# HABEXpico8.net
KiCad netlist of a schematic drawn in EAGLE
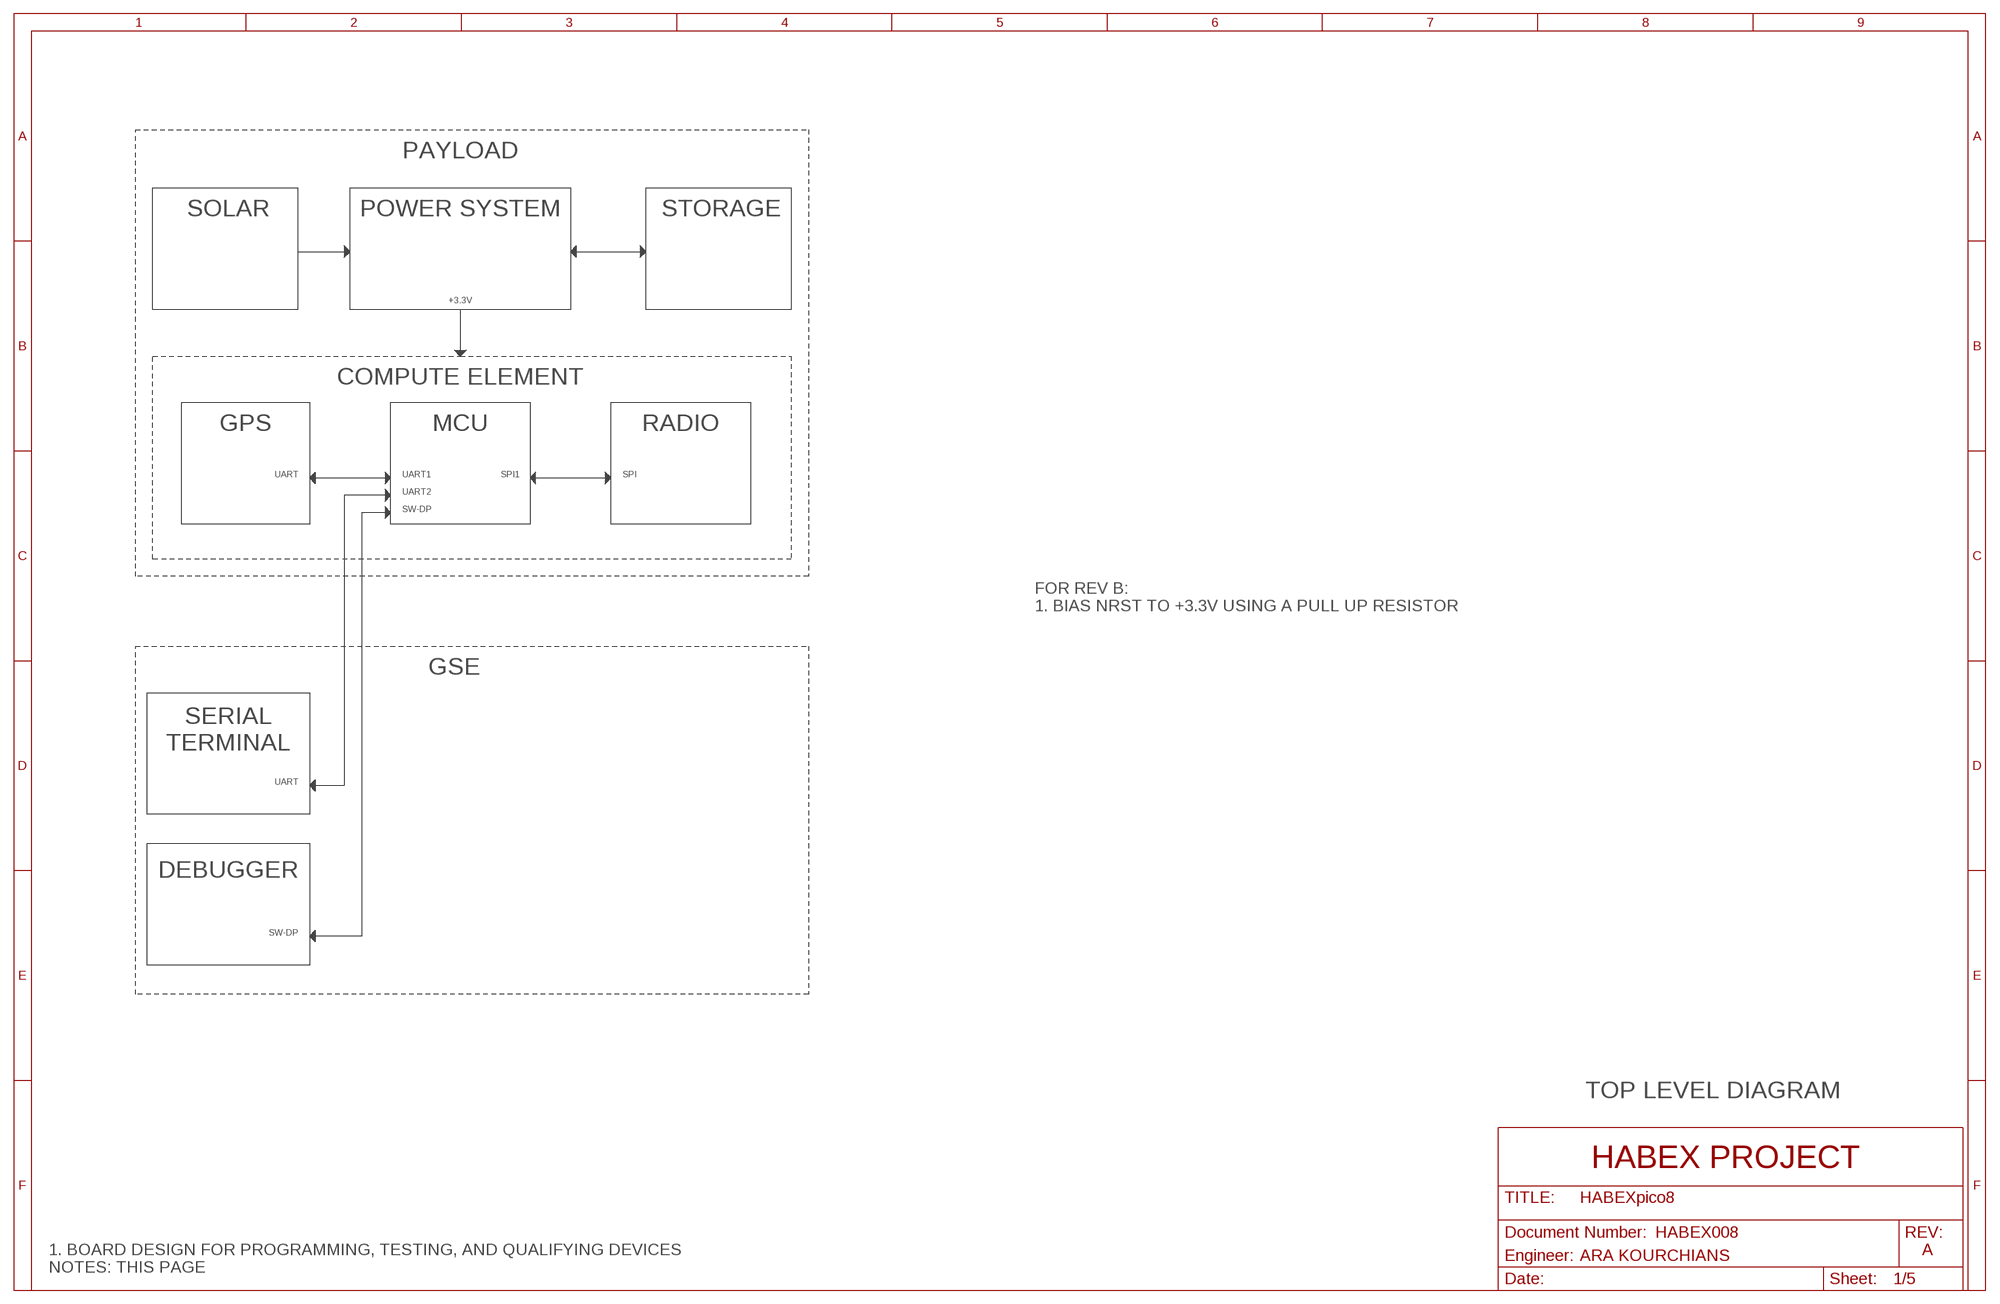
[diagram p0: schematic, sheet 1]
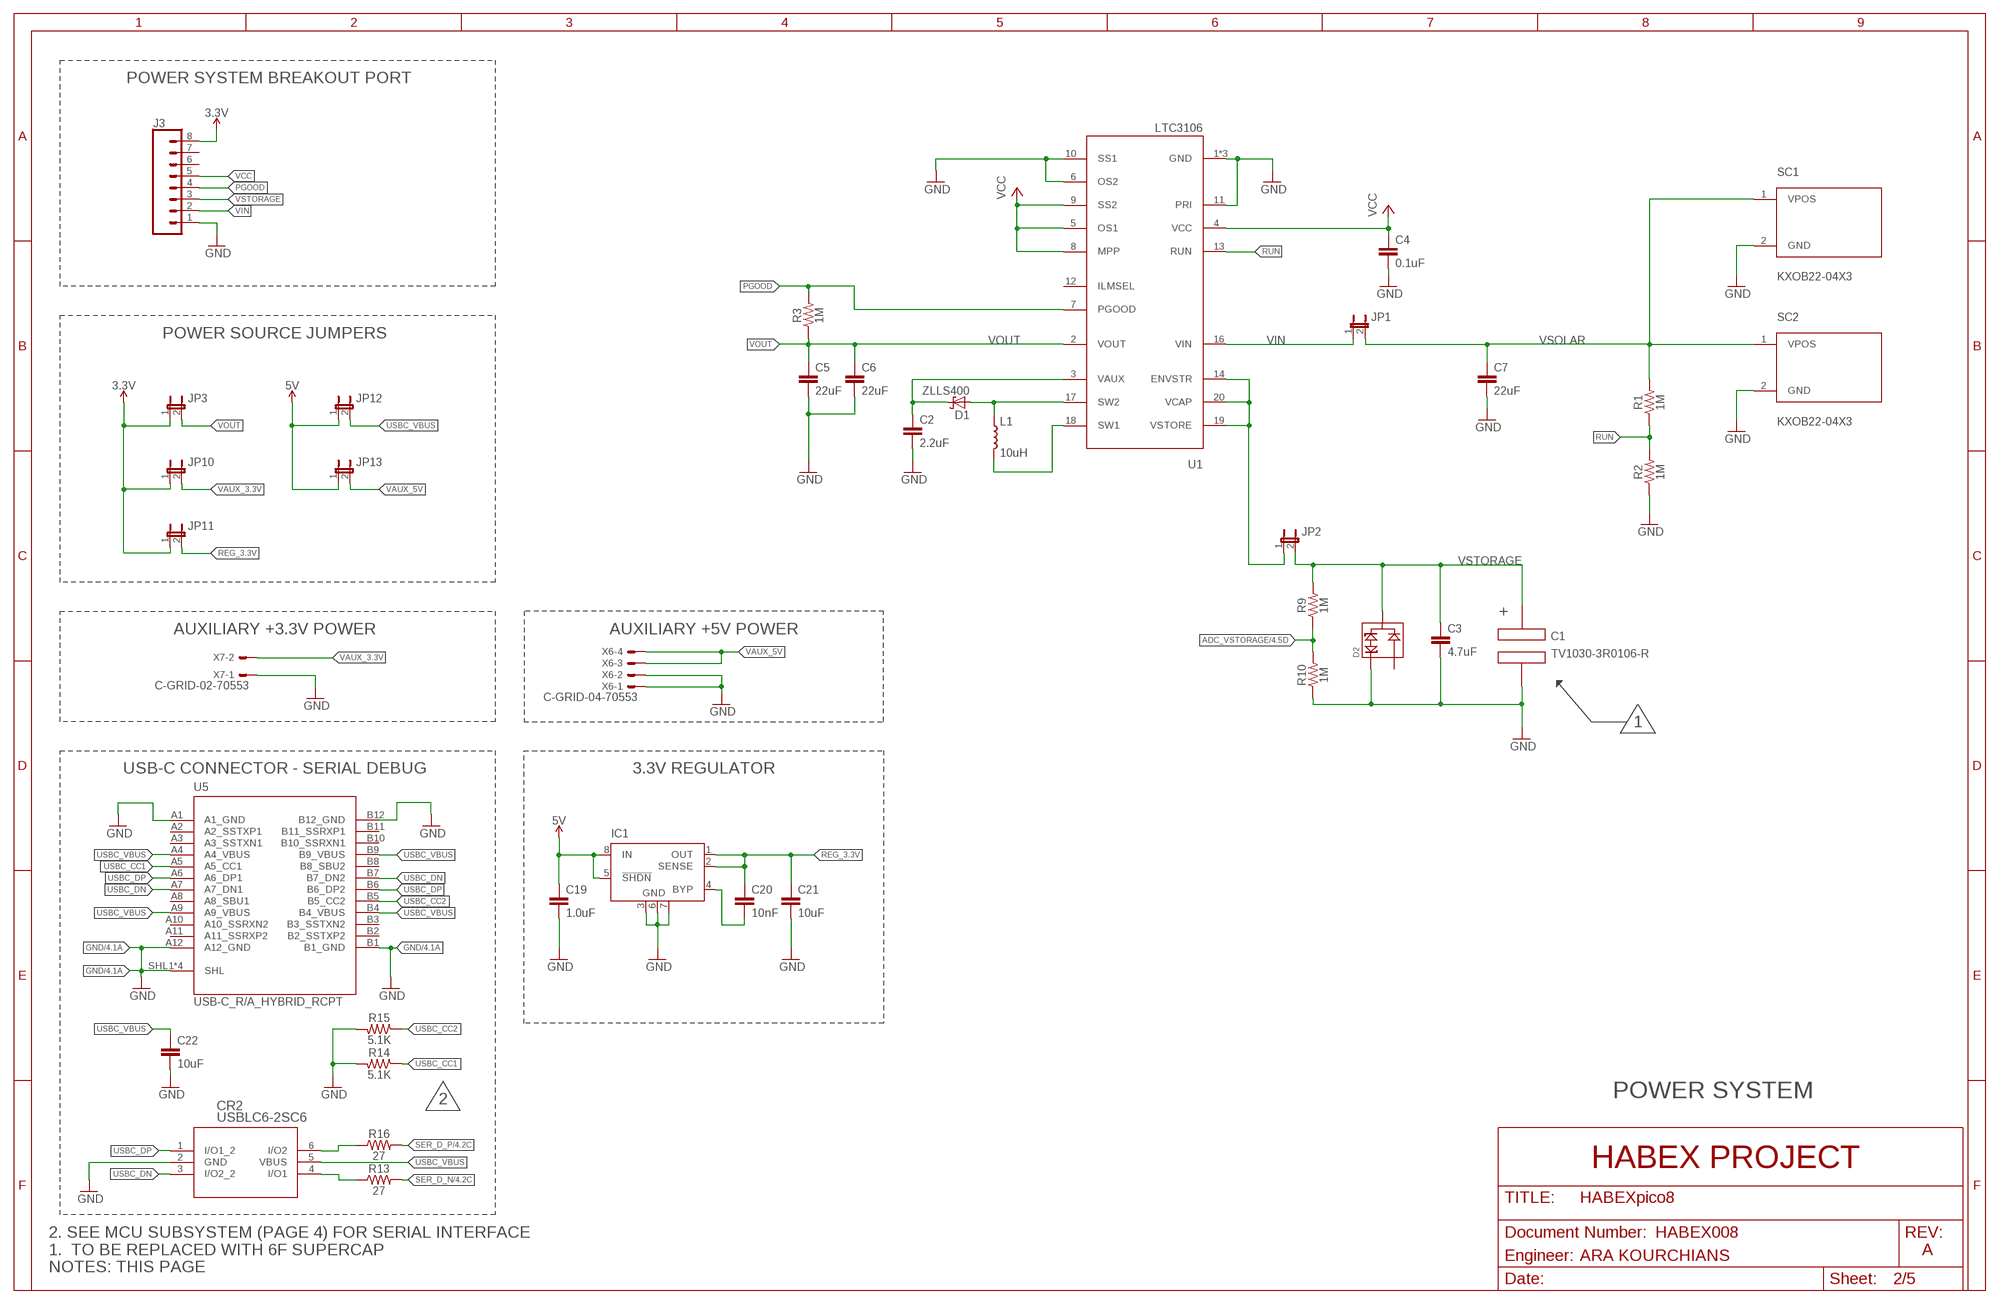
[diagram p1: schematic, sheet 2]
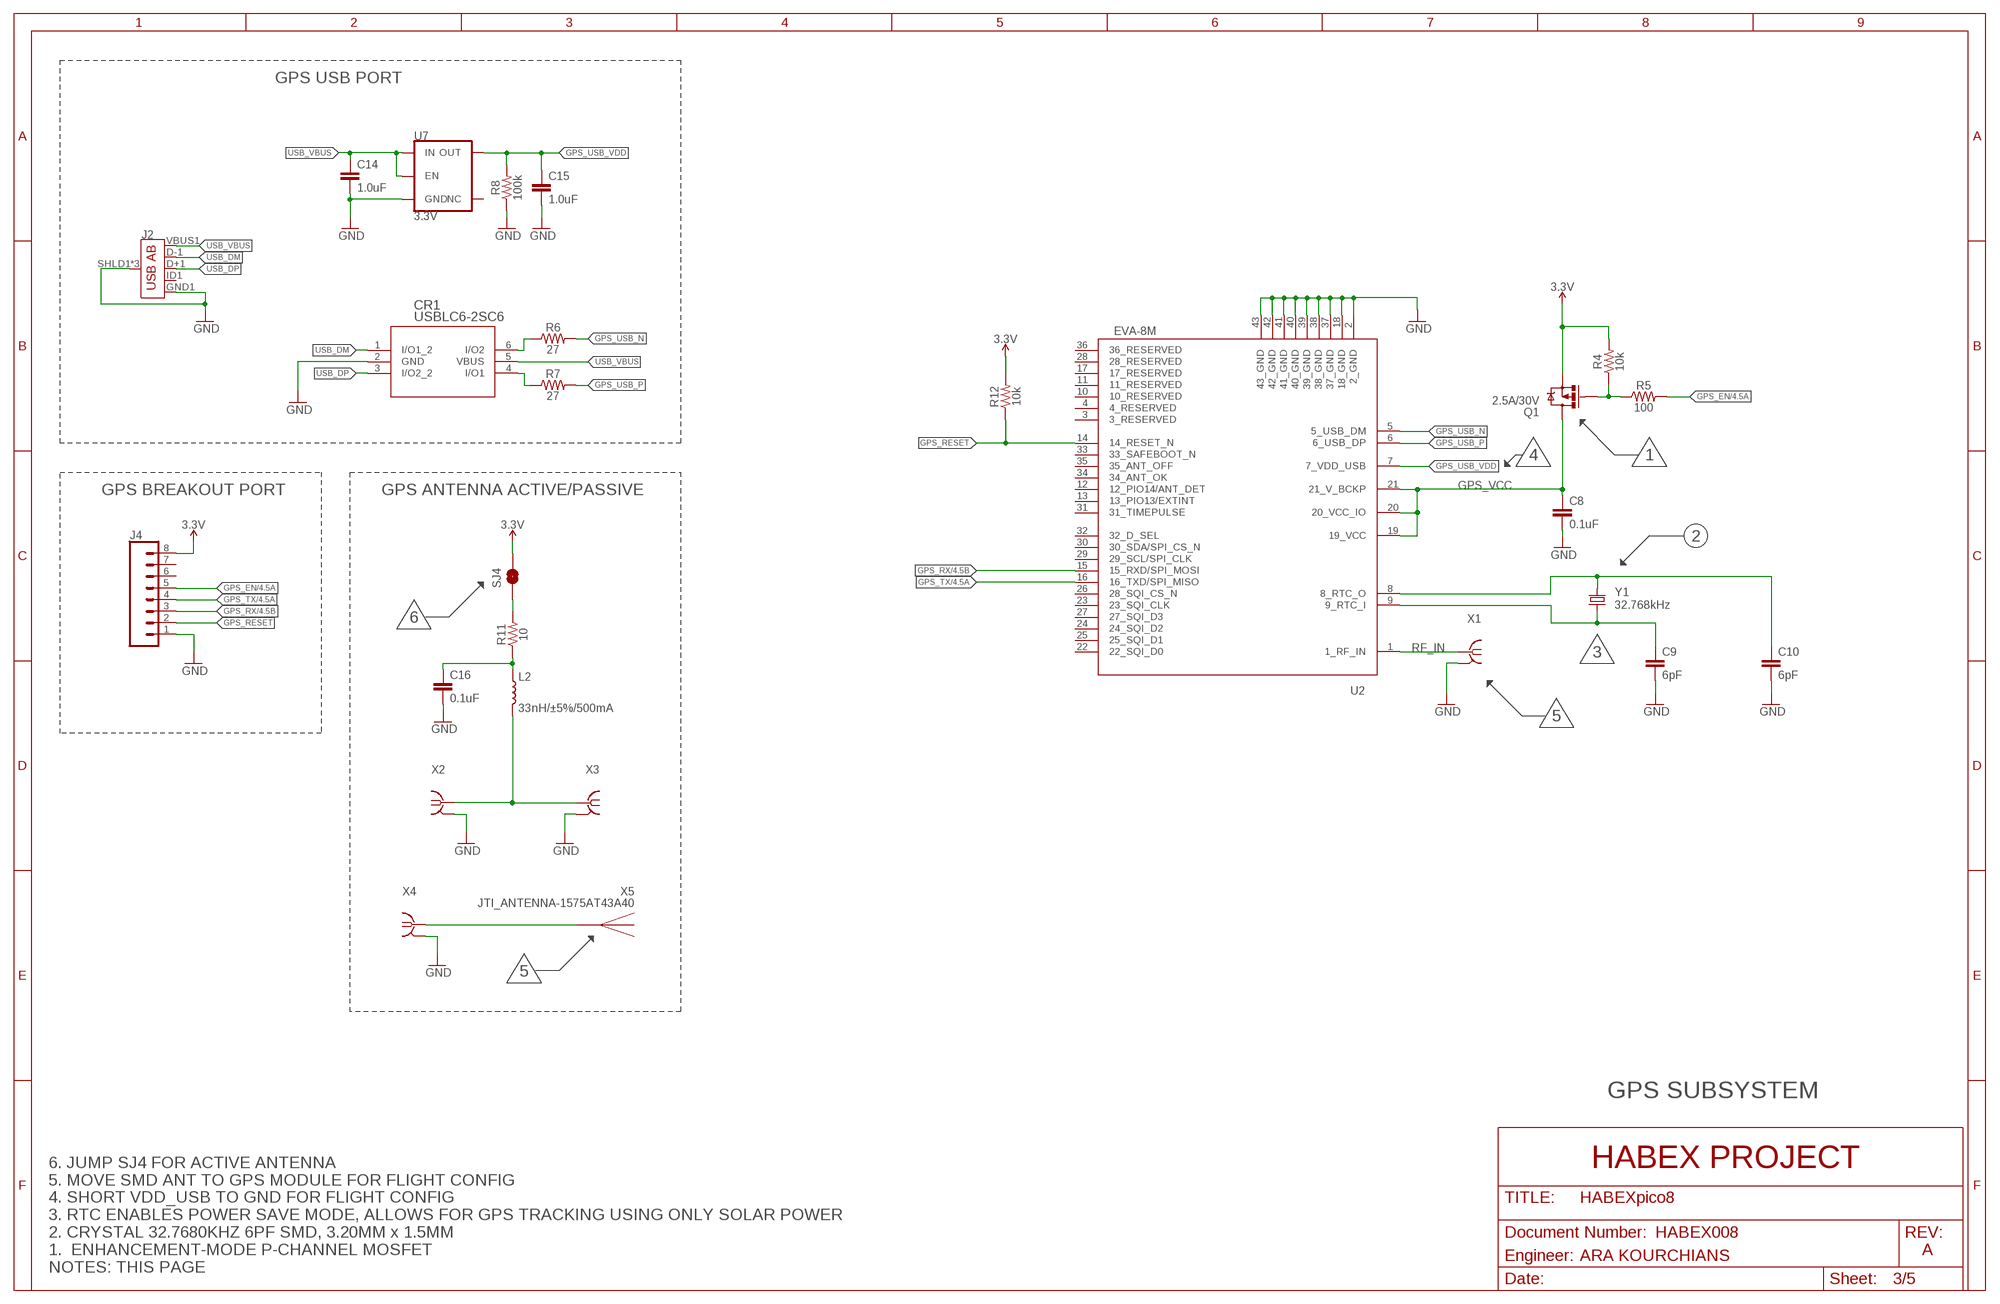
[diagram p2: schematic, sheet 3]
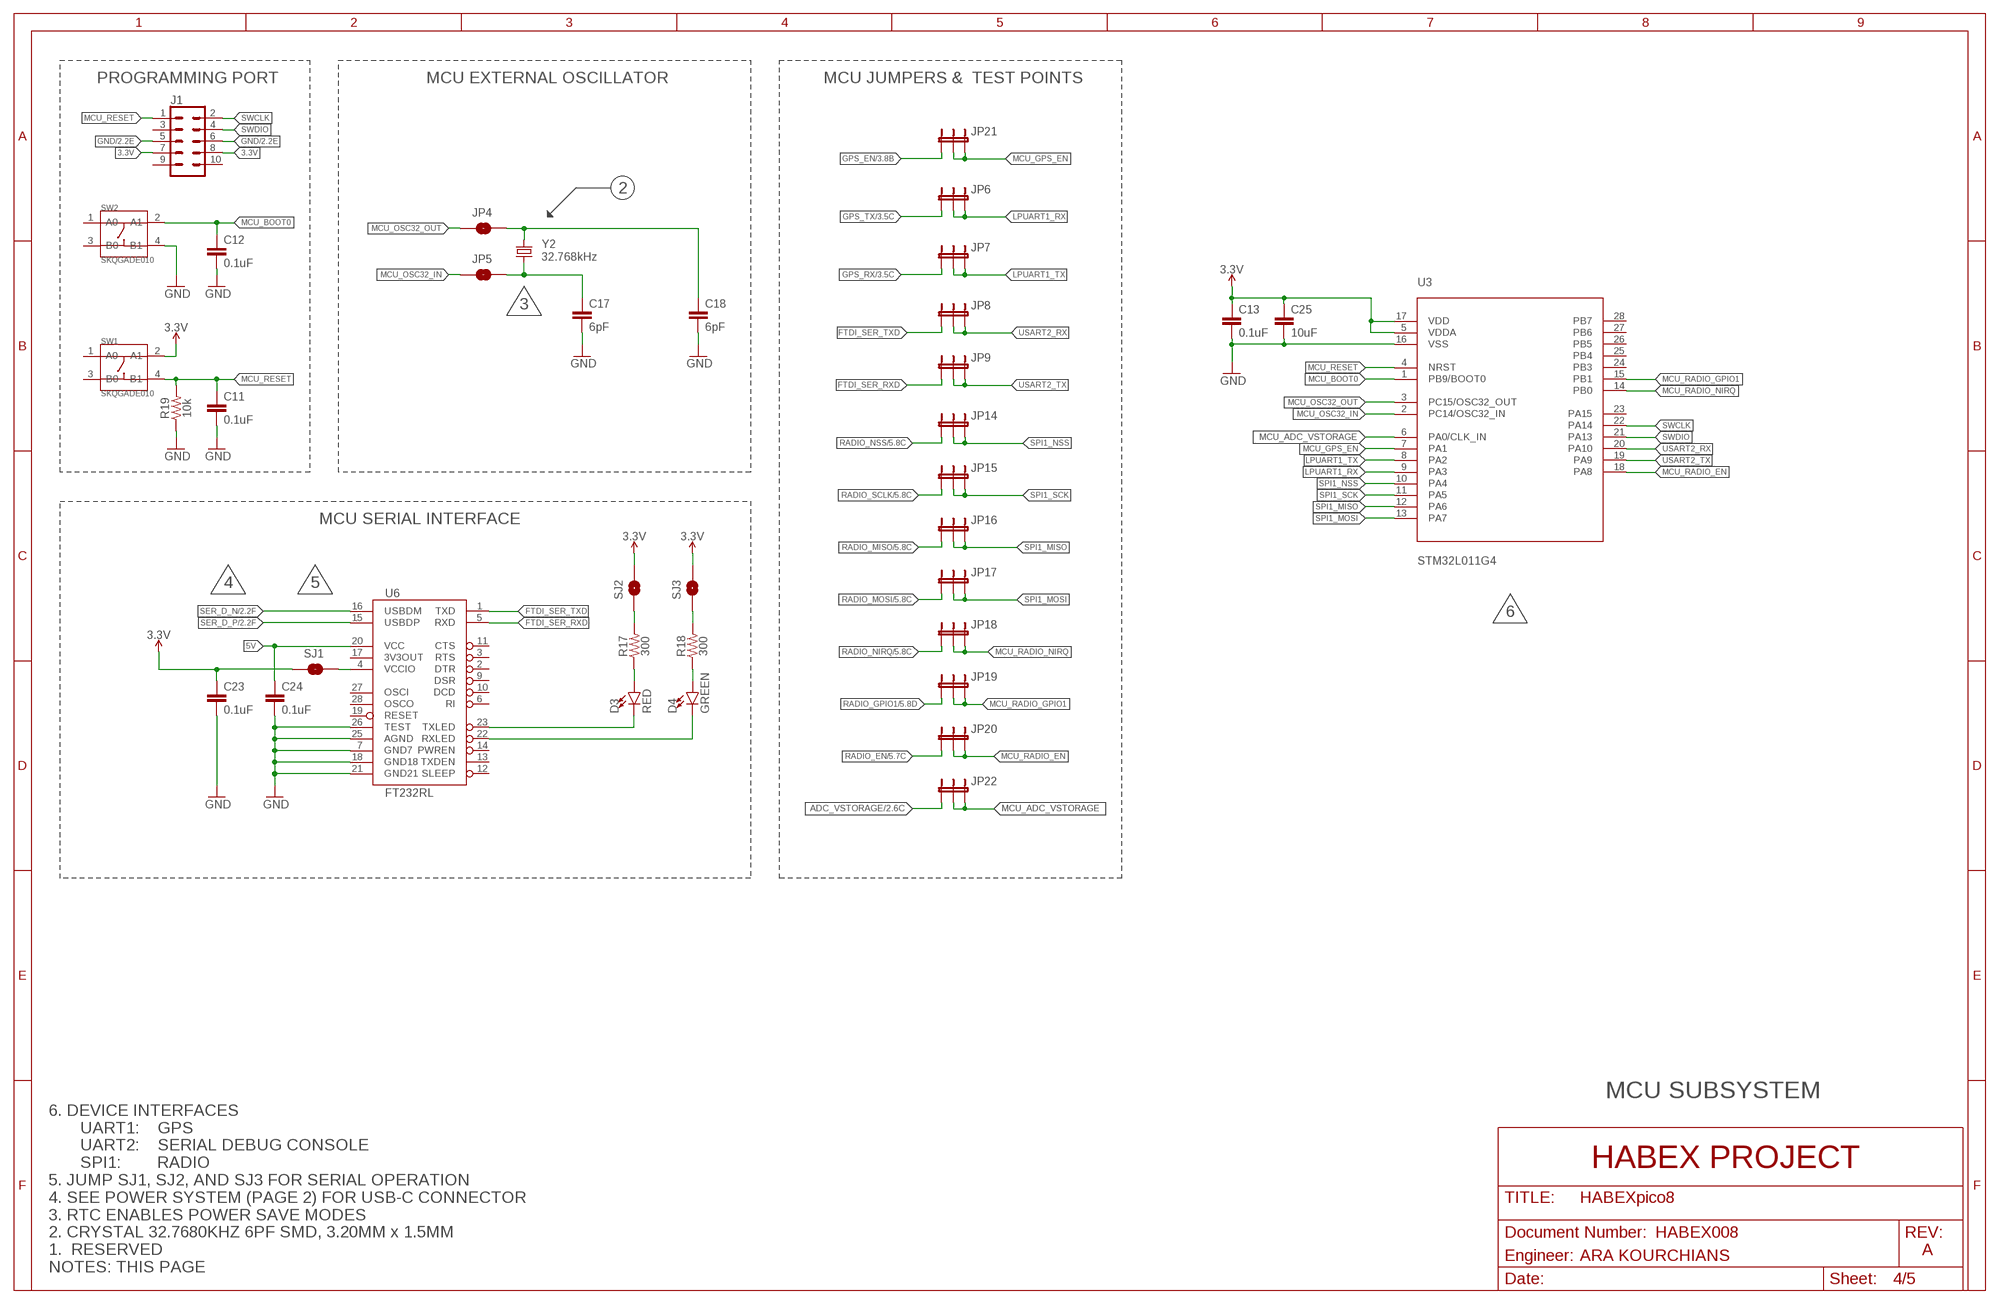
[diagram p3: schematic, sheet 4]
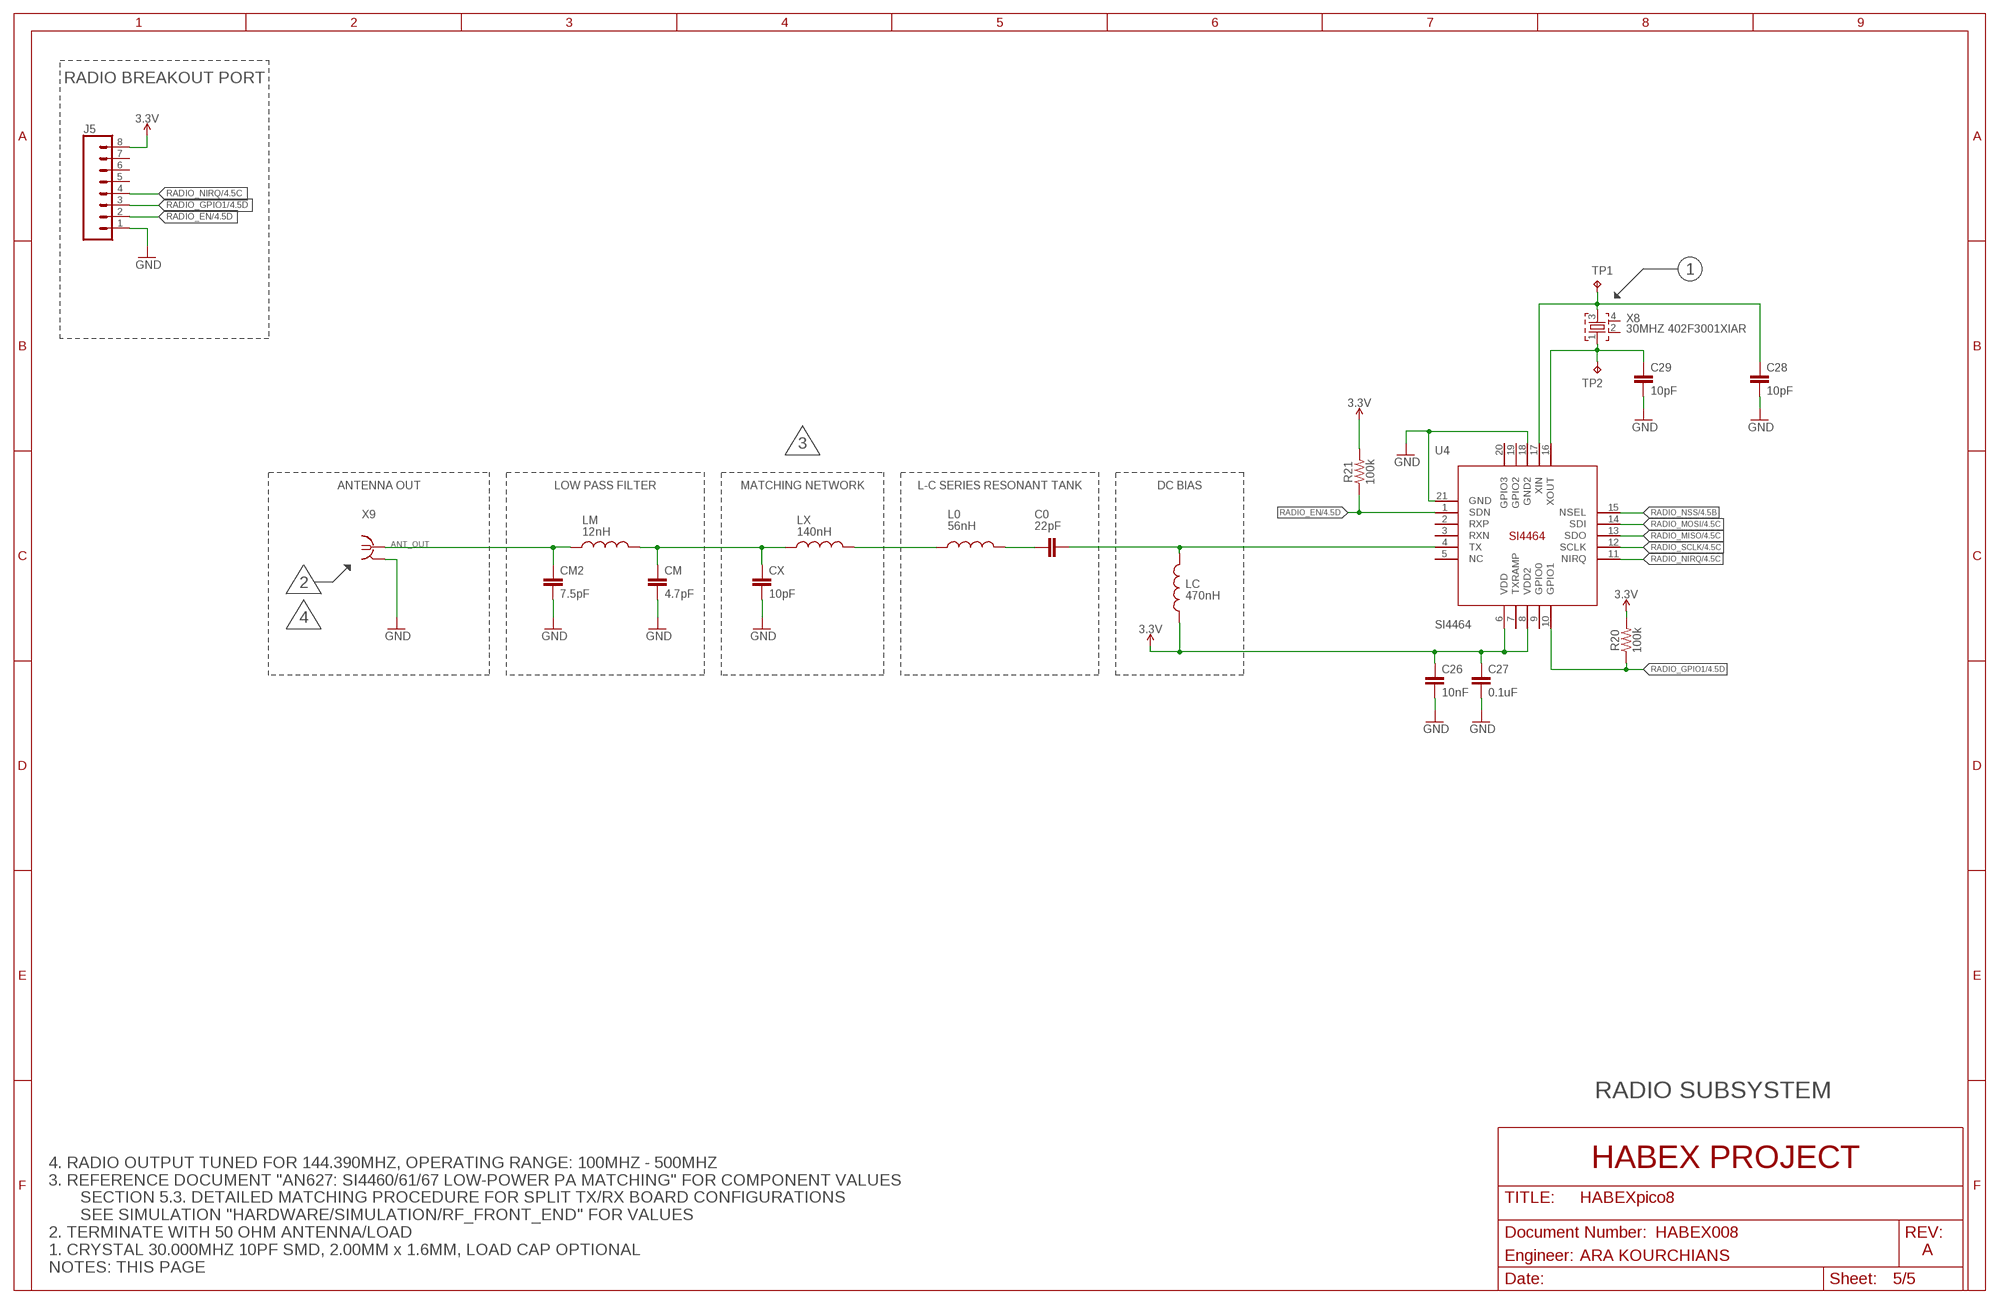
[diagram p4: schematic, sheet 5]

(export (version "E")
  (design (tool "Eeschema 10.0.6"))
  (components
    (comp (ref "C0")
      (value "22pF")
      (footprint "eagle-import:RESC0603_L")
      (libsource (lib "eagle-import") (part "CAPACITOR_0603_L"))
    )
    (comp (ref "C26")
      (value "10nF")
      (footprint "eagle-import:0603")
      (libsource (lib "eagle-import") (part "10NF-0603-50V-10%"))
    )
    (comp (ref "C27")
      (value "0.1uF")
      (footprint "eagle-import:0603")
      (libsource (lib "eagle-import") (part "0.1UF-0603-25V-5%"))
    )
    (comp (ref "C28")
      (value "10pF")
      (footprint "eagle-import:0603")
      (libsource (lib "eagle-import") (part "10PF-0603-50V-5%"))
    )
    (comp (ref "C29")
      (value "10pF")
      (footprint "eagle-import:0603")
      (libsource (lib "eagle-import") (part "10PF-0603-50V-5%"))
    )
    (comp (ref "CM")
      (value "4.7pF")
      (footprint "eagle-import:RESC0603_L")
      (libsource (lib "eagle-import") (part "CAPACITOR_0603_L"))
    )
    (comp (ref "CM2")
      (value "7.5pF")
      (footprint "eagle-import:RESC0603_L")
      (libsource (lib "eagle-import") (part "CAPACITOR_0603_L"))
    )
    (comp (ref "CX")
      (value "10pF")
      (footprint "eagle-import:RESC0603_L")
      (libsource (lib "eagle-import") (part "CAPACITOR_0603_L"))
    )
    (comp (ref "J5")
      (value "CONN_08\"")
      (footprint "eagle-import:1X08")
      (libsource (lib "eagle-import") (part "CONN_08{dblquote}"))
    )
    (comp (ref "L0")
      (value "56nH")
      (footprint "eagle-import:RESC0603_L")
      (libsource (lib "eagle-import") (part "INDUCTOR_0603_L"))
    )
    (comp (ref "LC")
      (value "470nH")
      (footprint "eagle-import:RESC0603_L")
      (libsource (lib "eagle-import") (part "INDUCTOR_0603_L"))
    )
    (comp (ref "LM")
      (value "12nH")
      (footprint "eagle-import:RESC0603_L")
      (libsource (lib "eagle-import") (part "INDUCTOR_0603_L"))
    )
    (comp (ref "LX")
      (value "140nH")
      (footprint "eagle-import:RESC0603_L")
      (libsource (lib "eagle-import") (part "INDUCTOR_0603_L"))
    )
    (comp (ref "R20")
      (value "100k")
      (footprint "eagle-import:0603")
      (libsource (lib "eagle-import") (part "100KOHM-0603-1/10W-1%"))
    )
    (comp (ref "R21")
      (value "100k")
      (footprint "eagle-import:0603")
      (libsource (lib "eagle-import") (part "100KOHM-0603-1/10W-1%"))
    )
    (comp (ref "TP1")
      (value "TPPAD1-13")
      (footprint "eagle-import:P1-13")
      (libsource (lib "eagle-import") (part "TPPAD1-13"))
    )
    (comp (ref "TP2")
      (value "TPPAD1-13")
      (footprint "eagle-import:P1-13")
      (libsource (lib "eagle-import") (part "TPPAD1-13"))
    )
    (comp (ref "U4")
      (value "SI4464")
      (footprint "eagle-import:QFN20+GNDPAD")
      (libsource (lib "eagle-import") (part "SI4464"))
    )
    (comp (ref "X8")
      (value "30MHZ 402F3001XIAR")
      (footprint "eagle-import:2.0X1.6-4-PAD")
      (libsource (lib "eagle-import") (part "CRYSTALS-GND-LID-IQXC-42"))
    )
    (comp (ref "X9")
      (value "BU-SMA-V")
      (footprint "eagle-import:BU-SMA-V")
      (libsource (lib "eagle-import") (part "BU-SMA-V"))
    )
    (comp (ref "C11")
      (value "0.1uF")
      (footprint "eagle-import:0603")
      (libsource (lib "eagle-import") (part "0.1UF-0603-25V-5%"))
    )
    (comp (ref "C12")
      (value "0.1uF")
      (footprint "eagle-import:0603")
      (libsource (lib "eagle-import") (part "0.1UF-0603-25V-5%"))
    )
    (comp (ref "C13")
      (value "0.1uF")
      (footprint "eagle-import:0603")
      (libsource (lib "eagle-import") (part "0.1UF-0603-25V-5%"))
    )
    (comp (ref "C17")
      (value "6pF")
      (footprint "eagle-import:C0603")
      (libsource (lib "eagle-import") (part "C-EUC0603"))
    )
    (comp (ref "C18")
      (value "6pF")
      (footprint "eagle-import:C0603")
      (libsource (lib "eagle-import") (part "C-EUC0603"))
    )
    (comp (ref "C23")
      (value "0.1uF")
      (footprint "eagle-import:0603")
      (libsource (lib "eagle-import") (part "0.1UF-0603-25V-5%"))
    )
    (comp (ref "C24")
      (value "0.1uF")
      (footprint "eagle-import:0603")
      (libsource (lib "eagle-import") (part "0.1UF-0603-25V-5%"))
    )
    (comp (ref "C25")
      (value "10uF")
      (footprint "eagle-import:0603")
      (libsource (lib "eagle-import") (part "10UF-0603-6.3V-20%"))
    )
    (comp (ref "D3")
      (value "RED")
      (footprint "eagle-import:LED-0603")
      (libsource (lib "eagle-import") (part "LED-RED0603"))
    )
    (comp (ref "D4")
      (value "GREEN")
      (footprint "eagle-import:LED-0603")
      (libsource (lib "eagle-import") (part "LED-GREEN0603"))
    )
    (comp (ref "J1")
      (value "CONN_05X2SHD")
      (footprint "eagle-import:2X5-SHROUDED")
      (libsource (lib "eagle-import") (part "CONN_05X2SHD"))
    )
    (comp (ref "JP4")
      (value "JUMPER-SMT_2_NO_SILK")
      (footprint "eagle-import:SMT-JUMPER_2_NO_SILK")
      (libsource (lib "eagle-import") (part "JUMPER-SMT_2_NO_SILK"))
    )
    (comp (ref "JP5")
      (value "JUMPER-SMT_2_NO_SILK")
      (footprint "eagle-import:SMT-JUMPER_2_NO_SILK")
      (libsource (lib "eagle-import") (part "JUMPER-SMT_2_NO_SILK"))
    )
    (comp (ref "JP6")
      (value "JUMPER-3PTH")
      (footprint "eagle-import:1X03")
      (libsource (lib "eagle-import") (part "JUMPER-3PTH"))
    )
    (comp (ref "JP7")
      (value "JUMPER-3PTH")
      (footprint "eagle-import:1X03")
      (libsource (lib "eagle-import") (part "JUMPER-3PTH"))
    )
    (comp (ref "JP8")
      (value "JUMPER-3PTH")
      (footprint "eagle-import:1X03")
      (libsource (lib "eagle-import") (part "JUMPER-3PTH"))
    )
    (comp (ref "JP9")
      (value "JUMPER-3PTH")
      (footprint "eagle-import:1X03")
      (libsource (lib "eagle-import") (part "JUMPER-3PTH"))
    )
    (comp (ref "JP14")
      (value "JUMPER-3PTH")
      (footprint "eagle-import:1X03")
      (libsource (lib "eagle-import") (part "JUMPER-3PTH"))
    )
    (comp (ref "JP15")
      (value "JUMPER-3PTH")
      (footprint "eagle-import:1X03")
      (libsource (lib "eagle-import") (part "JUMPER-3PTH"))
    )
    (comp (ref "JP16")
      (value "JUMPER-3PTH")
      (footprint "eagle-import:1X03")
      (libsource (lib "eagle-import") (part "JUMPER-3PTH"))
    )
    (comp (ref "JP17")
      (value "JUMPER-3PTH")
      (footprint "eagle-import:1X03")
      (libsource (lib "eagle-import") (part "JUMPER-3PTH"))
    )
    (comp (ref "JP18")
      (value "JUMPER-3PTH")
      (footprint "eagle-import:1X03")
      (libsource (lib "eagle-import") (part "JUMPER-3PTH"))
    )
    (comp (ref "JP19")
      (value "JUMPER-3PTH")
      (footprint "eagle-import:1X03")
      (libsource (lib "eagle-import") (part "JUMPER-3PTH"))
    )
    (comp (ref "JP20")
      (value "JUMPER-3PTH")
      (footprint "eagle-import:1X03")
      (libsource (lib "eagle-import") (part "JUMPER-3PTH"))
    )
    (comp (ref "JP21")
      (value "JUMPER-3PTH")
      (footprint "eagle-import:1X03")
      (libsource (lib "eagle-import") (part "JUMPER-3PTH"))
    )
    (comp (ref "JP22")
      (value "JUMPER-3PTH")
      (footprint "eagle-import:1X03")
      (libsource (lib "eagle-import") (part "JUMPER-3PTH"))
    )
    (comp (ref "R17")
      (value "300")
      (footprint "eagle-import:0603")
      (libsource (lib "eagle-import") (part "300OHM-0603-1/10W-1%"))
    )
    (comp (ref "R18")
      (value "300")
      (footprint "eagle-import:0603")
      (libsource (lib "eagle-import") (part "300OHM-0603-1/10W-1%"))
    )
    (comp (ref "R19")
      (value "10k")
      (footprint "eagle-import:0603")
      (libsource (lib "eagle-import") (part "10KOHM-0603-1/10W-1%"))
    )
    (comp (ref "SJ1")
      (value "SOLDERJUMPERNO")
      (footprint "eagle-import:SJ_2S-NO")
      (libsource (lib "eagle-import") (part "SOLDERJUMPERNO"))
    )
    (comp (ref "SJ2")
      (value "SOLDERJUMPERNO")
      (footprint "eagle-import:SJ_2S-NO")
      (libsource (lib "eagle-import") (part "SOLDERJUMPERNO"))
    )
    (comp (ref "SJ3")
      (value "SOLDERJUMPERNO")
      (footprint "eagle-import:SJ_2S-NO")
      (libsource (lib "eagle-import") (part "SOLDERJUMPERNO"))
    )
    (comp (ref "SW1")
      (value "SKQGADE010")
      (footprint "eagle-import:SW4-SMD-5.2X5.2X1.5MM")
      (libsource (lib "eagle-import") (part "SMD-BUTTON(4P-5.2X5.2X1.5MM-SKQGADE010)-SKQGADE010"))
    )
    (comp (ref "SW2")
      (value "SKQGADE010")
      (footprint "eagle-import:SW4-SMD-5.2X5.2X1.5MM")
      (libsource (lib "eagle-import") (part "SMD-BUTTON(4P-5.2X5.2X1.5MM-SKQGADE010)-SKQGADE010"))
    )
    (comp (ref "U3")
      (value "STM32L011G4")
      (footprint "eagle-import:UFQFPN28")
      (libsource (lib "eagle-import") (part "STM32L011G4"))
    )
    (comp (ref "U6")
      (value "FT232RL")
      (footprint "eagle-import:SSOP28DB")
      (libsource (lib "eagle-import") (part "FT232RLSSOP"))
    )
    (comp (ref "Y2")
      (value "32.768kHz")
      (footprint "eagle-import:CRYSTAL-SMD-3.2X1.5MM")
      (libsource (lib "eagle-import") (part "CRYSTAL-32.768KHZSMD-3.2X1.5"))
    )
    (comp (ref "C1")
      (value "TV1030-3R0106-R")
      (footprint "eagle-import:5.0MM-SUPERCAP")
      (libsource (lib "eagle-import") (part "TV1030-3R0106-R"))
    )
    (comp (ref "C2")
      (value "2.2uF")
      (footprint "eagle-import:0603")
      (libsource (lib "eagle-import") (part "2.2UF-0603-10V-20%"))
    )
    (comp (ref "C3")
      (value "4.7uF")
      (footprint "eagle-import:0603")
      (libsource (lib "eagle-import") (part "4.7UF0603"))
    )
    (comp (ref "C4")
      (value "0.1uF")
      (footprint "eagle-import:0603")
      (libsource (lib "eagle-import") (part "0.1UF-0603-25V-(+80/-20%)"))
    )
    (comp (ref "C5")
      (value "22uF")
      (footprint "eagle-import:0805")
      (libsource (lib "eagle-import") (part "22UF-0805-6.3V-20%"))
    )
    (comp (ref "C6")
      (value "22uF")
      (footprint "eagle-import:0805")
      (libsource (lib "eagle-import") (part "22UF-0805-6.3V-20%"))
    )
    (comp (ref "C7")
      (value "22uF")
      (footprint "eagle-import:0805")
      (libsource (lib "eagle-import") (part "22UF-0805-6.3V-20%"))
    )
    (comp (ref "C19")
      (value "1.0uF")
      (footprint "eagle-import:0603")
      (libsource (lib "eagle-import") (part "1.0UF-0603-16V-10%"))
    )
    (comp (ref "C20")
      (value "10nF")
      (footprint "eagle-import:0603")
      (libsource (lib "eagle-import") (part "10NF-0603-50V-10%"))
    )
    (comp (ref "C21")
      (value "10uF")
      (footprint "eagle-import:0603")
      (libsource (lib "eagle-import") (part "10UF-0603-6.3V-20%"))
    )
    (comp (ref "C22")
      (value "10uF")
      (footprint "eagle-import:0805")
      (libsource (lib "eagle-import") (part "10UF-0805-10V-10%"))
    )
    (comp (ref "CR2")
      (value "USBLC6-2SC6")
      (footprint "eagle-import:SOT23-6L")
      (fields (field (name "MANUFACTURER_PART_NUMBER") "USBLC62SC6"))
      (libsource (lib "eagle-import") (part "USBLC6-2SC6"))
    )
    (comp (ref "D1")
      (value "ZLLS400")
      (footprint "eagle-import:SOD-323")
      (libsource (lib "eagle-import") (part "ZLLS400"))
    )
    (comp (ref "D2")
      (value "SLVU2.8HTG")
      (footprint "eagle-import:SOT-23")
      (libsource (lib "eagle-import") (part "SLVU2.8HTG"))
    )
    (comp (ref "IC1")
      (value "LT1763CS8-3.3")
      (footprint "eagle-import:SOIC8")
      (libsource (lib "eagle-import") (part "LT1763CS8-3.3"))
    )
    (comp (ref "J3")
      (value "CONN_08\"")
      (footprint "eagle-import:1X08")
      (libsource (lib "eagle-import") (part "CONN_08{dblquote}"))
    )
    (comp (ref "JP1")
      (value "JUMPER-2PTH")
      (footprint "eagle-import:1X02")
      (libsource (lib "eagle-import") (part "JUMPER-2PTH"))
    )
    (comp (ref "JP2")
      (value "JUMPER-2PTH")
      (footprint "eagle-import:1X02")
      (libsource (lib "eagle-import") (part "JUMPER-2PTH"))
    )
    (comp (ref "JP3")
      (value "JUMPER-2PTH")
      (footprint "eagle-import:1X02")
      (libsource (lib "eagle-import") (part "JUMPER-2PTH"))
    )
    (comp (ref "JP10")
      (value "JUMPER-2PTH")
      (footprint "eagle-import:1X02")
      (libsource (lib "eagle-import") (part "JUMPER-2PTH"))
    )
    (comp (ref "JP11")
      (value "JUMPER-2PTH")
      (footprint "eagle-import:1X02")
      (libsource (lib "eagle-import") (part "JUMPER-2PTH"))
    )
    (comp (ref "JP12")
      (value "JUMPER-2PTH")
      (footprint "eagle-import:1X02")
      (libsource (lib "eagle-import") (part "JUMPER-2PTH"))
    )
    (comp (ref "JP13")
      (value "JUMPER-2PTH")
      (footprint "eagle-import:1X02")
      (libsource (lib "eagle-import") (part "JUMPER-2PTH"))
    )
    (comp (ref "L1")
      (value "10uH")
      (footprint "eagle-import:1210-INDUCTOR")
      (libsource (lib "eagle-import") (part "INDUCTOR-1210"))
    )
    (comp (ref "R1")
      (value "1M")
      (footprint "eagle-import:0603")
      (libsource (lib "eagle-import") (part "RESISTOR0603"))
    )
    (comp (ref "R2")
      (value "1M")
      (footprint "eagle-import:0603")
      (libsource (lib "eagle-import") (part "RESISTOR0603"))
    )
    (comp (ref "R3")
      (value "1M")
      (footprint "eagle-import:0603")
      (libsource (lib "eagle-import") (part "RESISTOR0603"))
    )
    (comp (ref "R9")
      (value "1M")
      (footprint "eagle-import:0603")
      (libsource (lib "eagle-import") (part "RESISTOR0603"))
    )
    (comp (ref "R10")
      (value "1M")
      (footprint "eagle-import:0603")
      (libsource (lib "eagle-import") (part "RESISTOR0603"))
    )
    (comp (ref "R13")
      (value "27")
      (footprint "eagle-import:0603")
      (libsource (lib "eagle-import") (part "27OHM-0603-1/10W-1%"))
    )
    (comp (ref "R14")
      (value "5.1K")
      (footprint "eagle-import:0603")
      (libsource (lib "eagle-import") (part "RESISTOR0603"))
    )
    (comp (ref "R15")
      (value "5.1K")
      (footprint "eagle-import:0603")
      (libsource (lib "eagle-import") (part "RESISTOR0603"))
    )
    (comp (ref "R16")
      (value "27")
      (footprint "eagle-import:0603")
      (libsource (lib "eagle-import") (part "27OHM-0603-1/10W-1%"))
    )
    (comp (ref "SC1")
      (value "KXOB22-04X3")
      (footprint "eagle-import:KX0B22")
      (libsource (lib "eagle-import") (part "KXOB22-04X3"))
    )
    (comp (ref "SC2")
      (value "KXOB22-04X3")
      (footprint "eagle-import:KX0B22")
      (libsource (lib "eagle-import") (part "KXOB22-04X3"))
    )
    (comp (ref "U1")
      (value "LTC3106")
      (footprint "eagle-import:UDC20QFN")
      (libsource (lib "eagle-import") (part "LTC3106"))
    )
    (comp (ref "U5")
      (value "USB-C_R/A_HYBRID_RCPT")
      (footprint "eagle-import:USB-C_R_A_HYBRID_RCPT")
      (libsource (lib "eagle-import") (part "USB-C_R/A_HYBRID"))
    )
    (comp (ref "X6")
      (value "C-GRID-04-70553")
      (footprint "eagle-import:70553-04")
      (fields (field (name "MF") "MOLEX"))
      (libsource (lib "eagle-import") (part "C-GRID-04-70553"))
    )
    (comp (ref "X7")
      (value "C-GRID-02-70553")
      (footprint "eagle-import:70553-02")
      (fields (field (name "MF") "MOLEX"))
      (libsource (lib "eagle-import") (part "C-GRID-02-70553"))
    )
    (comp (ref "C8")
      (value "0.1uF")
      (footprint "eagle-import:0603")
      (libsource (lib "eagle-import") (part "0.1UF-0603-25V-(+80/-20%)"))
    )
    (comp (ref "C9")
      (value "6pF")
      (footprint "eagle-import:C0603")
      (libsource (lib "eagle-import") (part "C-EUC0603"))
    )
    (comp (ref "C10")
      (value "6pF")
      (footprint "eagle-import:C0603")
      (libsource (lib "eagle-import") (part "C-EUC0603"))
    )
    (comp (ref "C14")
      (value "1.0uF")
      (footprint "eagle-import:0603")
      (libsource (lib "eagle-import") (part "1.0UF-0603-16V-10%"))
    )
    (comp (ref "C15")
      (value "1.0uF")
      (footprint "eagle-import:0603")
      (libsource (lib "eagle-import") (part "1.0UF-0603-16V-10%"))
    )
    (comp (ref "C16")
      (value "0.1uF")
      (footprint "eagle-import:0603")
      (libsource (lib "eagle-import") (part "0.1UF-0603-25V-5%"))
    )
    (comp (ref "CR1")
      (value "USBLC6-2SC6")
      (footprint "eagle-import:SOT23-6L")
      (fields (field (name "MANUFACTURER_PART_NUMBER") "USBLC62SC6"))
      (libsource (lib "eagle-import") (part "USBLC6-2SC6"))
    )
    (comp (ref "J2")
      (value "USB_AB_SMT")
      (footprint "eagle-import:USB-AB-MICRO-SMD")
      (libsource (lib "eagle-import") (part "USB_AB_SMT"))
    )
    (comp (ref "J4")
      (value "CONN_08\"")
      (footprint "eagle-import:1X08")
      (libsource (lib "eagle-import") (part "CONN_08{dblquote}"))
    )
    (comp (ref "L2")
      (value "33nH/±5%/500mA")
      (footprint "eagle-import:0603")
      (libsource (lib "eagle-import") (part "INDUCTOR-0603-33NH"))
    )
    (comp (ref "Q1")
      (value "2.5A/30V")
      (footprint "eagle-import:SOT23-3")
      (libsource (lib "eagle-import") (part "MOSFET-PCHANNELDMG2307L"))
    )
    (comp (ref "R4")
      (value "10k")
      (footprint "eagle-import:0603")
      (libsource (lib "eagle-import") (part "10KOHM-0603-1/10W-1%"))
    )
    (comp (ref "R5")
      (value "100")
      (footprint "eagle-import:0603")
      (libsource (lib "eagle-import") (part "100OHM-0603-1/10W-1%"))
    )
    (comp (ref "R6")
      (value "27")
      (footprint "eagle-import:0603")
      (libsource (lib "eagle-import") (part "27OHM-0603-1/10W-1%"))
    )
    (comp (ref "R7")
      (value "27")
      (footprint "eagle-import:0603")
      (libsource (lib "eagle-import") (part "27OHM-0603-1/10W-1%"))
    )
    (comp (ref "R8")
      (value "100k")
      (footprint "eagle-import:0603")
      (libsource (lib "eagle-import") (part "100KOHM-0603-1/10W-1%"))
    )
    (comp (ref "R11")
      (value "10")
      (footprint "eagle-import:1206")
      (libsource (lib "eagle-import") (part "10OHM-1206-1/4W-1%"))
    )
    (comp (ref "R12")
      (value "10k")
      (footprint "eagle-import:0603")
      (libsource (lib "eagle-import") (part "10KOHM-0603-1/10W-1%"))
    )
    (comp (ref "SJ4")
      (value "SOLDERJUMPERNO")
      (footprint "eagle-import:SJ_2S-NO")
      (libsource (lib "eagle-import") (part "SOLDERJUMPERNO"))
    )
    (comp (ref "U2")
      (value "EVA-8M")
      (footprint "eagle-import:EVA-8M")
      (libsource (lib "eagle-import") (part "EVA-8M"))
    )
    (comp (ref "U7")
      (value "3.3V")
      (footprint "eagle-import:SOT23-5")
      (libsource (lib "eagle-import") (part "V_REG_AP2112K-3.3V"))
    )
    (comp (ref "X1")
      (value "BU-SMA-V")
      (footprint "eagle-import:BU-SMA-V")
      (libsource (lib "eagle-import") (part "BU-SMA-V"))
    )
    (comp (ref "X2")
      (value "BU-SMA-V")
      (footprint "eagle-import:BU-SMA-V")
      (libsource (lib "eagle-import") (part "BU-SMA-V"))
    )
    (comp (ref "X3")
      (value "BU-SMA-V")
      (footprint "eagle-import:BU-SMA-V")
      (libsource (lib "eagle-import") (part "BU-SMA-V"))
    )
    (comp (ref "X4")
      (value "BU-SMA-V")
      (footprint "eagle-import:BU-SMA-V")
      (libsource (lib "eagle-import") (part "BU-SMA-V"))
    )
    (comp (ref "X5")
      (value "JTI_ANTENNA-1575AT43A40")
      (footprint "eagle-import:JTI_ANTENNA-1575AT43A40")
      (libsource (lib "eagle-import") (part "JTI_ANTENNA-1575AT43A40"))
    )
    (comp (ref "Y1")
      (value "32.768kHz")
      (footprint "eagle-import:CRYSTAL-SMD-3.2X1.5MM")
      (libsource (lib "eagle-import") (part "CRYSTAL-32.768KHZSMD-3.2X1.5"))
    )
  )
  (nets
    (net (code "1") (name "2") (class "Default")
      (node (ref "D2") (pin "2") (pinfunction "2_2") (pintype "power_in"))
    )
    (net (code "2") (name "3.3V") (class "Default")
      (node (ref "C13") (pin "1") (pinfunction "1_1") (pintype "passive"))
      (node (ref "C23") (pin "1") (pinfunction "1_1") (pintype "passive"))
      (node (ref "C25") (pin "1") (pinfunction "1_1") (pintype "passive"))
      (node (ref "C26") (pin "1") (pinfunction "1_1") (pintype "passive"))
      (node (ref "C27") (pin "1") (pinfunction "1_1") (pintype "passive"))
      (node (ref "J1") (pin "7") (pinfunction "7_7") (pintype "passive"))
      (node (ref "J1") (pin "8") (pinfunction "8_8") (pintype "passive"))
      (node (ref "J3") (pin "8") (pinfunction "8_8") (pintype "passive"))
      (node (ref "J4") (pin "8") (pinfunction "8_8") (pintype "passive"))
      (node (ref "J5") (pin "8") (pinfunction "8_8") (pintype "passive"))
      (node (ref "JP10") (pin "1") (pinfunction "1_1") (pintype "passive"))
      (node (ref "JP11") (pin "1") (pinfunction "1_1") (pintype "passive"))
      (node (ref "JP3") (pin "1") (pinfunction "1_1") (pintype "passive"))
      (node (ref "LC") (pin "1") (pinfunction "1_1") (pintype "passive"))
      (node (ref "Q1") (pin "2") (pinfunction "S_2") (pintype "passive"))
      (node (ref "R12") (pin "2") (pinfunction "2_2") (pintype "passive"))
      (node (ref "R20") (pin "2") (pinfunction "2_2") (pintype "passive"))
      (node (ref "R21") (pin "2") (pinfunction "2_2") (pintype "passive"))
      (node (ref "R4") (pin "2") (pinfunction "2_2") (pintype "passive"))
      (node (ref "SJ1") (pin "1") (pinfunction "1_1") (pintype "passive"))
      (node (ref "SJ2") (pin "2") (pinfunction "2_2") (pintype "passive"))
      (node (ref "SJ3") (pin "2") (pinfunction "2_2") (pintype "passive"))
      (node (ref "SJ4") (pin "2") (pinfunction "2_2") (pintype "passive"))
      (node (ref "SW1") (pin "2") (pinfunction "A1_2") (pintype "bidirectional"))
      (node (ref "U3") (pin "17") (pinfunction "VDD_17") (pintype "bidirectional"))
      (node (ref "U3") (pin "5") (pinfunction "VDDA_5") (pintype "bidirectional"))
      (node (ref "U4") (pin "6") (pinfunction "VDD_6") (pintype "bidirectional"))
      (node (ref "U4") (pin "8") (pinfunction "VDD2_8") (pintype "bidirectional"))
    )
    (net (code "3") (name "5V") (class "Default")
      (node (ref "C19") (pin "1") (pinfunction "1_1") (pintype "passive"))
      (node (ref "C24") (pin "1") (pinfunction "1_1") (pintype "passive"))
      (node (ref "IC1") (pin "5") (pinfunction "~{SHDN}_5") (pintype "input"))
      (node (ref "IC1") (pin "8") (pinfunction "IN_8") (pintype "input"))
      (node (ref "JP12") (pin "1") (pinfunction "1_1") (pintype "passive"))
      (node (ref "JP13") (pin "1") (pinfunction "1_1") (pintype "passive"))
      (node (ref "U6") (pin "20") (pinfunction "VCC_20") (pintype "power_in"))
    )
    (net (code "4") (name "ADC_VSTORAGE") (class "Default")
      (node (ref "JP22") (pin "1") (pinfunction "1_1") (pintype "passive"))
      (node (ref "R10") (pin "2") (pinfunction "2_2") (pintype "passive"))
      (node (ref "R9") (pin "1") (pinfunction "1_1") (pintype "passive"))
    )
    (net (code "5") (name "ANT_OUT") (class "Default")
      (node (ref "CM2") (pin "1") (pinfunction "1_1") (pintype "passive"))
      (node (ref "LM") (pin "1") (pinfunction "1_1") (pintype "passive"))
      (node (ref "X9") (pin "1") (pinfunction "1_1") (pintype "passive"))
    )
    (net (code "6") (name "FTDI_SER_RXD") (class "Default")
      (node (ref "JP9") (pin "1") (pinfunction "1_1") (pintype "passive"))
      (node (ref "U6") (pin "5") (pinfunction "RXD_5") (pintype "input"))
    )
    (net (code "7") (name "FTDI_SER_TXD") (class "Default")
      (node (ref "JP8") (pin "1") (pinfunction "1_1") (pintype "passive"))
      (node (ref "U6") (pin "1") (pinfunction "TXD_1") (pintype "output"))
    )
    (net (code "8") (name "GND") (class "Default")
      (node (ref "C1") (pin "2") (pinfunction "CAP_NEG_2") (pintype "bidirectional"))
      (node (ref "C10") (pin "2") (pinfunction "2_2") (pintype "passive"))
      (node (ref "C11") (pin "2") (pinfunction "2_2") (pintype "passive"))
      (node (ref "C12") (pin "2") (pinfunction "2_2") (pintype "passive"))
      (node (ref "C13") (pin "2") (pinfunction "2_2") (pintype "passive"))
      (node (ref "C14") (pin "2") (pinfunction "2_2") (pintype "passive"))
      (node (ref "C15") (pin "2") (pinfunction "2_2") (pintype "passive"))
      (node (ref "C16") (pin "2") (pinfunction "2_2") (pintype "passive"))
      (node (ref "C17") (pin "2") (pinfunction "2_2") (pintype "passive"))
      (node (ref "C18") (pin "2") (pinfunction "2_2") (pintype "passive"))
      (node (ref "C19") (pin "2") (pinfunction "2_2") (pintype "passive"))
      (node (ref "C2") (pin "2") (pinfunction "2_2") (pintype "passive"))
      (node (ref "C21") (pin "2") (pinfunction "2_2") (pintype "passive"))
      (node (ref "C22") (pin "2") (pinfunction "2_2") (pintype "passive"))
      (node (ref "C23") (pin "2") (pinfunction "2_2") (pintype "passive"))
      (node (ref "C24") (pin "2") (pinfunction "2_2") (pintype "passive"))
      (node (ref "C25") (pin "2") (pinfunction "2_2") (pintype "passive"))
      (node (ref "C26") (pin "2") (pinfunction "2_2") (pintype "passive"))
      (node (ref "C27") (pin "2") (pinfunction "2_2") (pintype "passive"))
      (node (ref "C28") (pin "2") (pinfunction "2_2") (pintype "passive"))
      (node (ref "C29") (pin "2") (pinfunction "2_2") (pintype "passive"))
      (node (ref "C3") (pin "2") (pinfunction "2_2") (pintype "passive"))
      (node (ref "C4") (pin "2") (pinfunction "2_2") (pintype "passive"))
      (node (ref "C5") (pin "2") (pinfunction "2_2") (pintype "passive"))
      (node (ref "C6") (pin "2") (pinfunction "2_2") (pintype "passive"))
      (node (ref "C7") (pin "2") (pinfunction "2_2") (pintype "passive"))
      (node (ref "C8") (pin "2") (pinfunction "2_2") (pintype "passive"))
      (node (ref "C9") (pin "2") (pinfunction "2_2") (pintype "passive"))
      (node (ref "CM") (pin "2") (pinfunction "2_2") (pintype "passive"))
      (node (ref "CM2") (pin "2") (pinfunction "2_2") (pintype "passive"))
      (node (ref "CR1") (pin "2") (pinfunction "GND_2") (pintype "power_in"))
      (node (ref "CR2") (pin "2") (pinfunction "GND_2") (pintype "power_in"))
      (node (ref "CX") (pin "2") (pinfunction "2_2") (pintype "passive"))
      (node (ref "D2") (pin "1") (pinfunction "1_1") (pintype "power_in"))
      (node (ref "IC1") (pin "3") (pinfunction "GND_3") (pintype "power_in"))
      (node (ref "IC1") (pin "6") (pinfunction "GND_6") (pintype "power_in"))
      (node (ref "IC1") (pin "7") (pinfunction "GND_7") (pintype "power_in"))
      (node (ref "J1") (pin "5") (pinfunction "5_5") (pintype "passive"))
      (node (ref "J1") (pin "6") (pinfunction "6_6") (pintype "passive"))
      (node (ref "J2") (pin "GND1") (pinfunction "GND_GND1") (pintype "power_in"))
      (node (ref "J2") (pin "SHLD1") (pinfunction "SHIELD_SHLD1") (pintype "bidirectional"))
      (node (ref "J2") (pin "SHLD2") (pinfunction "SHIELD_SHLD2") (pintype "bidirectional"))
      (node (ref "J2") (pin "SHLD3") (pinfunction "SHIELD_SHLD3") (pintype "bidirectional"))
      (node (ref "J3") (pin "1") (pinfunction "1_1") (pintype "passive"))
      (node (ref "J4") (pin "1") (pinfunction "1_1") (pintype "passive"))
      (node (ref "J5") (pin "1") (pinfunction "1_1") (pintype "passive"))
      (node (ref "R10") (pin "1") (pinfunction "1_1") (pintype "passive"))
      (node (ref "R14") (pin "2") (pinfunction "2_2") (pintype "passive"))
      (node (ref "R15") (pin "2") (pinfunction "2_2") (pintype "passive"))
      (node (ref "R19") (pin "1") (pinfunction "1_1") (pintype "passive"))
      (node (ref "R2") (pin "1") (pinfunction "1_1") (pintype "passive"))
      (node (ref "R8") (pin "1") (pinfunction "1_1") (pintype "passive"))
      (node (ref "SC1") (pin "2") (pinfunction "GND_2") (pintype "bidirectional"))
      (node (ref "SC2") (pin "2") (pinfunction "GND_2") (pintype "bidirectional"))
      (node (ref "SW2") (pin "4") (pinfunction "B1_4") (pintype "bidirectional"))
      (node (ref "U1") (pin "1") (pinfunction "GND_1") (pintype "bidirectional"))
      (node (ref "U1") (pin "10") (pinfunction "SS1_10") (pintype "bidirectional"))
      (node (ref "U1") (pin "11") (pinfunction "PRI_11") (pintype "bidirectional"))
      (node (ref "U1") (pin "15") (pinfunction "GND_15") (pintype "bidirectional"))
      (node (ref "U1") (pin "21") (pinfunction "GND_21") (pintype "bidirectional"))
      (node (ref "U1") (pin "6") (pinfunction "OS2_6") (pintype "bidirectional"))
      (node (ref "U2") (pin "18") (pinfunction "18_GND_18") (pintype "bidirectional"))
      (node (ref "U2") (pin "2") (pinfunction "2_GND_2") (pintype "bidirectional"))
      (node (ref "U2") (pin "37") (pinfunction "37_GND_37") (pintype "bidirectional"))
      (node (ref "U2") (pin "38") (pinfunction "38_GND_38") (pintype "bidirectional"))
      (node (ref "U2") (pin "39") (pinfunction "39_GND_39") (pintype "bidirectional"))
      (node (ref "U2") (pin "40") (pinfunction "40_GND_40") (pintype "bidirectional"))
      (node (ref "U2") (pin "41") (pinfunction "41_GND_41") (pintype "bidirectional"))
      (node (ref "U2") (pin "42") (pinfunction "42_GND_42") (pintype "bidirectional"))
      (node (ref "U2") (pin "43") (pinfunction "43_GND_43") (pintype "bidirectional"))
      (node (ref "U3") (pin "16") (pinfunction "VSS_16") (pintype "bidirectional"))
      (node (ref "U4") (pin "18") (pinfunction "GND2_18") (pintype "bidirectional"))
      (node (ref "U4") (pin "21") (pinfunction "GND_21") (pintype "bidirectional"))
      (node (ref "U5") (pin "A1") (pinfunction "A1_GND_A1") (pintype "bidirectional"))
      (node (ref "U5") (pin "A12") (pinfunction "A12_GND_A12") (pintype "bidirectional"))
      (node (ref "U5") (pin "B1") (pinfunction "B1_GND_B1") (pintype "bidirectional"))
      (node (ref "U5") (pin "B12") (pinfunction "B12_GND_B12") (pintype "bidirectional"))
      (node (ref "U5") (pin "SHL1") (pinfunction "SHL_SHL1") (pintype "bidirectional"))
      (node (ref "U5") (pin "SHL2") (pinfunction "SHL_SHL2") (pintype "bidirectional"))
      (node (ref "U5") (pin "SHL3") (pinfunction "SHL_SHL3") (pintype "bidirectional"))
      (node (ref "U5") (pin "SHL4") (pinfunction "SHL_SHL4") (pintype "bidirectional"))
      (node (ref "U6") (pin "18") (pinfunction "GND18_18") (pintype "power_in"))
      (node (ref "U6") (pin "21") (pinfunction "GND21_21") (pintype "power_in"))
      (node (ref "U6") (pin "25") (pinfunction "AGND_25") (pintype "power_in"))
      (node (ref "U6") (pin "26") (pinfunction "TEST_26") (pintype "input"))
      (node (ref "U6") (pin "7") (pinfunction "GND7_7") (pintype "power_in"))
      (node (ref "U7") (pin "2") (pinfunction "GND_2") (pintype "input"))
      (node (ref "X1") (pin "2") (pinfunction "2_2") (pintype "passive"))
      (node (ref "X1") (pin "3") (pinfunction "2_3") (pintype "passive"))
      (node (ref "X1") (pin "4") (pinfunction "2_4") (pintype "passive"))
      (node (ref "X1") (pin "5") (pinfunction "2_5") (pintype "passive"))
      (node (ref "X2") (pin "2") (pinfunction "2_2") (pintype "passive"))
      (node (ref "X2") (pin "3") (pinfunction "2_3") (pintype "passive"))
      (node (ref "X2") (pin "4") (pinfunction "2_4") (pintype "passive"))
      (node (ref "X2") (pin "5") (pinfunction "2_5") (pintype "passive"))
      (node (ref "X3") (pin "2") (pinfunction "2_2") (pintype "passive"))
      (node (ref "X3") (pin "3") (pinfunction "2_3") (pintype "passive"))
      (node (ref "X3") (pin "4") (pinfunction "2_4") (pintype "passive"))
      (node (ref "X3") (pin "5") (pinfunction "2_5") (pintype "passive"))
      (node (ref "X4") (pin "2") (pinfunction "2_2") (pintype "passive"))
      (node (ref "X4") (pin "3") (pinfunction "2_3") (pintype "passive"))
      (node (ref "X4") (pin "4") (pinfunction "2_4") (pintype "passive"))
      (node (ref "X4") (pin "5") (pinfunction "2_5") (pintype "passive"))
      (node (ref "X6") (pin "1") (pinfunction "S_1") (pintype "passive"))
      (node (ref "X6") (pin "2") (pinfunction "S_2") (pintype "passive"))
      (node (ref "X7") (pin "1") (pinfunction "S_1") (pintype "passive"))
      (node (ref "X9") (pin "2") (pinfunction "2_2") (pintype "passive"))
      (node (ref "X9") (pin "3") (pinfunction "2_3") (pintype "passive"))
      (node (ref "X9") (pin "4") (pinfunction "2_4") (pintype "passive"))
      (node (ref "X9") (pin "5") (pinfunction "2_5") (pintype "passive"))
    )
    (net (code "9") (name "GPS_EN") (class "Default")
      (node (ref "J4") (pin "5") (pinfunction "5_5") (pintype "passive"))
      (node (ref "JP21") (pin "1") (pinfunction "1_1") (pintype "passive"))
      (node (ref "R5") (pin "2") (pinfunction "2_2") (pintype "passive"))
    )
    (net (code "10") (name "GPS_RESET") (class "Default")
      (node (ref "J4") (pin "2") (pinfunction "2_2") (pintype "passive"))
      (node (ref "R12") (pin "1") (pinfunction "1_1") (pintype "passive"))
      (node (ref "U2") (pin "14") (pinfunction "14_RESET_N_14") (pintype "bidirectional"))
    )
    (net (code "11") (name "GPS_RX") (class "Default")
      (node (ref "J4") (pin "3") (pinfunction "3_3") (pintype "passive"))
      (node (ref "JP7") (pin "1") (pinfunction "1_1") (pintype "passive"))
      (node (ref "U2") (pin "15") (pinfunction "15_RXD/SPI_MOSI_15") (pintype "bidirectional"))
    )
    (net (code "12") (name "GPS_TX") (class "Default")
      (node (ref "J4") (pin "4") (pinfunction "4_4") (pintype "passive"))
      (node (ref "JP6") (pin "1") (pinfunction "1_1") (pintype "passive"))
      (node (ref "U2") (pin "16") (pinfunction "16_TXD/SPI_MISO_16") (pintype "bidirectional"))
    )
    (net (code "13") (name "GPS_USB_N") (class "Default")
      (node (ref "R6") (pin "2") (pinfunction "2_2") (pintype "passive"))
      (node (ref "U2") (pin "5") (pinfunction "5_USB_DM_5") (pintype "bidirectional"))
    )
    (net (code "14") (name "GPS_USB_P") (class "Default")
      (node (ref "R7") (pin "2") (pinfunction "2_2") (pintype "passive"))
      (node (ref "U2") (pin "6") (pinfunction "6_USB_DP_6") (pintype "bidirectional"))
    )
    (net (code "15") (name "GPS_USB_VDD") (class "Default")
      (node (ref "C15") (pin "1") (pinfunction "1_1") (pintype "passive"))
      (node (ref "R8") (pin "2") (pinfunction "2_2") (pintype "passive"))
      (node (ref "U2") (pin "7") (pinfunction "7_VDD_USB_7") (pintype "bidirectional"))
      (node (ref "U7") (pin "5") (pinfunction "OUT_5") (pintype "passive"))
    )
    (net (code "16") (name "GPS_VCC") (class "Default")
      (node (ref "C8") (pin "1") (pinfunction "1_1") (pintype "passive"))
      (node (ref "Q1") (pin "3") (pinfunction "D_3") (pintype "passive"))
      (node (ref "U2") (pin "19") (pinfunction "19_VCC_19") (pintype "bidirectional"))
      (node (ref "U2") (pin "20") (pinfunction "20_VCC_IO_20") (pintype "bidirectional"))
      (node (ref "U2") (pin "21") (pinfunction "21_V_BCKP_21") (pintype "bidirectional"))
    )
    (net (code "17") (name "LPUART1_RX") (class "Default")
      (node (ref "JP6") (pin "2") (pinfunction "2_2") (pintype "passive"))
      (node (ref "JP6") (pin "3") (pinfunction "3_3") (pintype "passive"))
      (node (ref "U3") (pin "9") (pinfunction "PA3_9") (pintype "bidirectional"))
    )
    (net (code "18") (name "LPUART1_TX") (class "Default")
      (node (ref "JP7") (pin "2") (pinfunction "2_2") (pintype "passive"))
      (node (ref "JP7") (pin "3") (pinfunction "3_3") (pintype "passive"))
      (node (ref "U3") (pin "8") (pinfunction "PA2_8") (pintype "bidirectional"))
    )
    (net (code "19") (name "MCU_ADC_VSTORAGE") (class "Default")
      (node (ref "JP22") (pin "2") (pinfunction "2_2") (pintype "passive"))
      (node (ref "JP22") (pin "3") (pinfunction "3_3") (pintype "passive"))
      (node (ref "U3") (pin "6") (pinfunction "PA0/CLK_IN_6") (pintype "bidirectional"))
    )
    (net (code "20") (name "MCU_BOOT0") (class "Default")
      (node (ref "C12") (pin "1") (pinfunction "1_1") (pintype "passive"))
      (node (ref "SW2") (pin "2") (pinfunction "A1_2") (pintype "bidirectional"))
      (node (ref "U3") (pin "1") (pinfunction "PB9/BOOT0_1") (pintype "bidirectional"))
    )
    (net (code "21") (name "MCU_GPS_EN") (class "Default")
      (node (ref "JP21") (pin "2") (pinfunction "2_2") (pintype "passive"))
      (node (ref "JP21") (pin "3") (pinfunction "3_3") (pintype "passive"))
      (node (ref "U3") (pin "7") (pinfunction "PA1_7") (pintype "bidirectional"))
    )
    (net (code "22") (name "MCU_OSC32_IN") (class "Default")
      (node (ref "JP5") (pin "1") (pinfunction "1_1") (pintype "passive"))
      (node (ref "U3") (pin "2") (pinfunction "PC14/OSC32_IN_2") (pintype "bidirectional"))
    )
    (net (code "23") (name "MCU_OSC32_OUT") (class "Default")
      (node (ref "JP4") (pin "1") (pinfunction "1_1") (pintype "passive"))
      (node (ref "U3") (pin "3") (pinfunction "PC15/OSC32_OUT_3") (pintype "bidirectional"))
    )
    (net (code "24") (name "MCU_RADIO_EN") (class "Default")
      (node (ref "JP20") (pin "2") (pinfunction "2_2") (pintype "passive"))
      (node (ref "JP20") (pin "3") (pinfunction "3_3") (pintype "passive"))
      (node (ref "U3") (pin "18") (pinfunction "PA8_18") (pintype "bidirectional"))
    )
    (net (code "25") (name "MCU_RADIO_GPIO1") (class "Default")
      (node (ref "JP19") (pin "2") (pinfunction "2_2") (pintype "passive"))
      (node (ref "JP19") (pin "3") (pinfunction "3_3") (pintype "passive"))
      (node (ref "U3") (pin "15") (pinfunction "PB1_15") (pintype "bidirectional"))
    )
    (net (code "26") (name "MCU_RADIO_NIRQ") (class "Default")
      (node (ref "JP18") (pin "2") (pinfunction "2_2") (pintype "passive"))
      (node (ref "JP18") (pin "3") (pinfunction "3_3") (pintype "passive"))
      (node (ref "U3") (pin "14") (pinfunction "PB0_14") (pintype "bidirectional"))
    )
    (net (code "27") (name "MCU_RESET") (class "Default")
      (node (ref "C11") (pin "1") (pinfunction "1_1") (pintype "passive"))
      (node (ref "J1") (pin "1") (pinfunction "1_1") (pintype "passive"))
      (node (ref "R19") (pin "2") (pinfunction "2_2") (pintype "passive"))
      (node (ref "SW1") (pin "4") (pinfunction "B1_4") (pintype "bidirectional"))
      (node (ref "U3") (pin "4") (pinfunction "NRST_4") (pintype "bidirectional"))
    )
    (net (code "28") (name "Net-(C0-Pad2)") (class "Default")
      (node (ref "C0") (pin "2") (pinfunction "2_2") (pintype "passive"))
      (node (ref "L0") (pin "2") (pinfunction "2_2") (pintype "passive"))
    )
    (net (code "29") (name "Net-(C16-Pad1)") (class "Default")
      (node (ref "C16") (pin "1") (pinfunction "1_1") (pintype "passive"))
      (node (ref "L2") (pin "1") (pinfunction "1_1") (pintype "passive"))
      (node (ref "R11") (pin "1") (pinfunction "1_1") (pintype "passive"))
    )
    (net (code "30") (name "Net-(CM-Pad1)") (class "Default")
      (node (ref "CM") (pin "1") (pinfunction "1_1") (pintype "passive"))
      (node (ref "CX") (pin "1") (pinfunction "1_1") (pintype "passive"))
      (node (ref "LM") (pin "2") (pinfunction "2_2") (pintype "passive"))
      (node (ref "LX") (pin "1") (pinfunction "1_1") (pintype "passive"))
    )
    (net (code "31") (name "Net-(CR1-I{slash}O1)") (class "Default")
      (node (ref "CR1") (pin "4") (pinfunction "I/O1_4") (pintype "bidirectional"))
      (node (ref "R7") (pin "1") (pinfunction "1_1") (pintype "passive"))
    )
    (net (code "32") (name "Net-(CR1-I{slash}O2)") (class "Default")
      (node (ref "CR1") (pin "6") (pinfunction "I/O2_6") (pintype "bidirectional"))
      (node (ref "R6") (pin "1") (pinfunction "1_1") (pintype "passive"))
    )
    (net (code "33") (name "Net-(CR2-I{slash}O1)") (class "Default")
      (node (ref "CR2") (pin "4") (pinfunction "I/O1_4") (pintype "bidirectional"))
      (node (ref "R13") (pin "1") (pinfunction "1_1") (pintype "passive"))
    )
    (net (code "34") (name "Net-(CR2-I{slash}O2)") (class "Default")
      (node (ref "CR2") (pin "6") (pinfunction "I/O2_6") (pintype "bidirectional"))
      (node (ref "R16") (pin "1") (pinfunction "1_1") (pintype "passive"))
    )
    (net (code "35") (name "Net-(D3-PadA)") (class "Default")
      (node (ref "D3") (pin "A") (pinfunction "A_A") (pintype "passive"))
      (node (ref "R17") (pin "1") (pinfunction "1_1") (pintype "passive"))
    )
    (net (code "36") (name "Net-(D4-PadA)") (class "Default")
      (node (ref "D4") (pin "A") (pinfunction "A_A") (pintype "passive"))
      (node (ref "R18") (pin "1") (pinfunction "1_1") (pintype "passive"))
    )
    (net (code "37") (name "Net-(IC1-BYP)") (class "Default")
      (node (ref "C20") (pin "2") (pinfunction "2_2") (pintype "passive"))
      (node (ref "IC1") (pin "4") (pinfunction "BYP_4") (pintype "input"))
    )
    (net (code "38") (name "Net-(L0-Pad1)") (class "Default")
      (node (ref "L0") (pin "1") (pinfunction "1_1") (pintype "passive"))
      (node (ref "LX") (pin "2") (pinfunction "2_2") (pintype "passive"))
    )
    (net (code "39") (name "Net-(L2-Pad2)") (class "Default")
      (node (ref "L2") (pin "2") (pinfunction "2_2") (pintype "passive"))
      (node (ref "X2") (pin "1") (pinfunction "1_1") (pintype "passive"))
      (node (ref "X3") (pin "1") (pinfunction "1_1") (pintype "passive"))
    )
    (net (code "40") (name "Net-(Q1-G)") (class "Default")
      (node (ref "Q1") (pin "1") (pinfunction "G_1") (pintype "passive"))
      (node (ref "R4") (pin "1") (pinfunction "1_1") (pintype "passive"))
      (node (ref "R5") (pin "1") (pinfunction "1_1") (pintype "passive"))
    )
    (net (code "41") (name "Net-(R11-Pad2)") (class "Default")
      (node (ref "R11") (pin "2") (pinfunction "2_2") (pintype "passive"))
      (node (ref "SJ4") (pin "1") (pinfunction "1_1") (pintype "passive"))
    )
    (net (code "42") (name "Net-(R17-Pad2)") (class "Default")
      (node (ref "R17") (pin "2") (pinfunction "2_2") (pintype "passive"))
      (node (ref "SJ2") (pin "1") (pinfunction "1_1") (pintype "passive"))
    )
    (net (code "43") (name "Net-(R18-Pad2)") (class "Default")
      (node (ref "R18") (pin "2") (pinfunction "2_2") (pintype "passive"))
      (node (ref "SJ3") (pin "1") (pinfunction "1_1") (pintype "passive"))
    )
    (net (code "44") (name "Net-(U1-ENVSTR)") (class "Default")
      (node (ref "JP2") (pin "1") (pinfunction "1_1") (pintype "passive"))
      (node (ref "U1") (pin "14") (pinfunction "ENVSTR_14") (pintype "bidirectional"))
      (node (ref "U1") (pin "19") (pinfunction "VSTORE_19") (pintype "bidirectional"))
      (node (ref "U1") (pin "20") (pinfunction "VCAP_20") (pintype "bidirectional"))
    )
    (net (code "45") (name "Net-(U1-SW1)") (class "Default")
      (node (ref "L1") (pin "2") (pinfunction "2_2") (pintype "passive"))
      (node (ref "U1") (pin "18") (pinfunction "SW1_18") (pintype "bidirectional"))
    )
    (net (code "46") (name "Net-(U1-SW2)") (class "Default")
      (node (ref "D1") (pin "A") (pinfunction "A_A") (pintype "passive"))
      (node (ref "L1") (pin "1") (pinfunction "1_1") (pintype "passive"))
      (node (ref "U1") (pin "17") (pinfunction "SW2_17") (pintype "bidirectional"))
    )
    (net (code "47") (name "Net-(U1-VAUX)") (class "Default")
      (node (ref "C2") (pin "1") (pinfunction "1_1") (pintype "passive"))
      (node (ref "D1") (pin "C") (pinfunction "C_C") (pintype "passive"))
      (node (ref "U1") (pin "3") (pinfunction "VAUX_3") (pintype "bidirectional"))
    )
    (net (code "48") (name "Net-(U2-8_RTC_O)") (class "Default")
      (node (ref "C10") (pin "1") (pinfunction "1_1") (pintype "passive"))
      (node (ref "U2") (pin "8") (pinfunction "8_RTC_O_8") (pintype "bidirectional"))
      (node (ref "Y1") (pin "P$2") (pinfunction "2_P$2") (pintype "passive"))
    )
    (net (code "49") (name "Net-(U2-9_RTC_I)") (class "Default")
      (node (ref "C9") (pin "1") (pinfunction "1_1") (pintype "passive"))
      (node (ref "U2") (pin "9") (pinfunction "9_RTC_I_9") (pintype "bidirectional"))
      (node (ref "Y1") (pin "P$1") (pinfunction "1_P$1") (pintype "passive"))
    )
    (net (code "50") (name "Net-(U4-TX)") (class "Default")
      (node (ref "C0") (pin "1") (pinfunction "1_1") (pintype "passive"))
      (node (ref "LC") (pin "2") (pinfunction "2_2") (pintype "passive"))
      (node (ref "U4") (pin "4") (pinfunction "TX_4") (pintype "bidirectional"))
    )
    (net (code "51") (name "Net-(U4-XIN)") (class "Default")
      (node (ref "C28") (pin "1") (pinfunction "1_1") (pintype "passive"))
      (node (ref "TP1") (pin "TP") (pinfunction "TP_TP") (pintype "input"))
      (node (ref "U4") (pin "17") (pinfunction "XIN_17") (pintype "bidirectional"))
      (node (ref "X8") (pin "3") (pinfunction "3_3") (pintype "passive"))
    )
    (net (code "52") (name "Net-(U4-XOUT)") (class "Default")
      (node (ref "C29") (pin "1") (pinfunction "1_1") (pintype "passive"))
      (node (ref "TP2") (pin "TP") (pinfunction "TP_TP") (pintype "input"))
      (node (ref "U4") (pin "16") (pinfunction "XOUT_16") (pintype "bidirectional"))
      (node (ref "X8") (pin "1") (pinfunction "1_1") (pintype "passive"))
    )
    (net (code "53") (name "Net-(U6-RXLED)") (class "Default")
      (node (ref "D4") (pin "C") (pinfunction "C_C") (pintype "passive"))
      (node (ref "U6") (pin "22") (pinfunction "RXLED_22") (pintype "input"))
    )
    (net (code "54") (name "Net-(U6-TXLED)") (class "Default")
      (node (ref "D3") (pin "C") (pinfunction "C_C") (pintype "passive"))
      (node (ref "U6") (pin "23") (pinfunction "TXLED_23") (pintype "input"))
    )
    (net (code "55") (name "Net-(U6-VCCIO)") (class "Default")
      (node (ref "SJ1") (pin "2") (pinfunction "2_2") (pintype "passive"))
      (node (ref "U6") (pin "4") (pinfunction "VCCIO_4") (pintype "power_in"))
    )
    (net (code "56") (name "Net-(X4-Pad1)") (class "Default")
      (node (ref "X4") (pin "1") (pinfunction "1_1") (pintype "passive"))
      (node (ref "X5") (pin "FEED") (pinfunction "FEED_FEED") (pintype "bidirectional"))
    )
    (net (code "57") (name "Net-(Y2-1)") (class "Default")
      (node (ref "C17") (pin "1") (pinfunction "1_1") (pintype "passive"))
      (node (ref "JP5") (pin "2") (pinfunction "2_2") (pintype "passive"))
      (node (ref "Y2") (pin "P$1") (pinfunction "1_P$1") (pintype "passive"))
    )
    (net (code "58") (name "Net-(Y2-2)") (class "Default")
      (node (ref "C18") (pin "1") (pinfunction "1_1") (pintype "passive"))
      (node (ref "JP4") (pin "2") (pinfunction "2_2") (pintype "passive"))
      (node (ref "Y2") (pin "P$2") (pinfunction "2_P$2") (pintype "passive"))
    )
    (net (code "59") (name "PGOOD") (class "Default")
      (node (ref "J3") (pin "4") (pinfunction "4_4") (pintype "passive"))
      (node (ref "R3") (pin "2") (pinfunction "2_2") (pintype "passive"))
      (node (ref "U1") (pin "7") (pinfunction "PGOOD_7") (pintype "bidirectional"))
    )
    (net (code "60") (name "RADIO_EN") (class "Default")
      (node (ref "J5") (pin "2") (pinfunction "2_2") (pintype "passive"))
      (node (ref "JP20") (pin "1") (pinfunction "1_1") (pintype "passive"))
      (node (ref "R21") (pin "1") (pinfunction "1_1") (pintype "passive"))
      (node (ref "U4") (pin "1") (pinfunction "SDN_1") (pintype "bidirectional"))
    )
    (net (code "61") (name "RADIO_GPIO1") (class "Default")
      (node (ref "J5") (pin "3") (pinfunction "3_3") (pintype "passive"))
      (node (ref "JP19") (pin "1") (pinfunction "1_1") (pintype "passive"))
      (node (ref "R20") (pin "1") (pinfunction "1_1") (pintype "passive"))
      (node (ref "U4") (pin "10") (pinfunction "GPIO1_10") (pintype "bidirectional"))
    )
    (net (code "62") (name "RADIO_MISO") (class "Default")
      (node (ref "JP16") (pin "1") (pinfunction "1_1") (pintype "passive"))
      (node (ref "U4") (pin "13") (pinfunction "SDO_13") (pintype "bidirectional"))
    )
    (net (code "63") (name "RADIO_MOSI") (class "Default")
      (node (ref "JP17") (pin "1") (pinfunction "1_1") (pintype "passive"))
      (node (ref "U4") (pin "14") (pinfunction "SDI_14") (pintype "bidirectional"))
    )
    (net (code "64") (name "RADIO_NIRQ") (class "Default")
      (node (ref "J5") (pin "4") (pinfunction "4_4") (pintype "passive"))
      (node (ref "JP18") (pin "1") (pinfunction "1_1") (pintype "passive"))
      (node (ref "U4") (pin "11") (pinfunction "NIRQ_11") (pintype "bidirectional"))
    )
    (net (code "65") (name "RADIO_NSS") (class "Default")
      (node (ref "JP14") (pin "1") (pinfunction "1_1") (pintype "passive"))
      (node (ref "U4") (pin "15") (pinfunction "NSEL_15") (pintype "bidirectional"))
    )
    (net (code "66") (name "RADIO_SCLK") (class "Default")
      (node (ref "JP15") (pin "1") (pinfunction "1_1") (pintype "passive"))
      (node (ref "U4") (pin "12") (pinfunction "SCLK_12") (pintype "bidirectional"))
    )
    (net (code "67") (name "REG_3.3V") (class "Default")
      (node (ref "C20") (pin "1") (pinfunction "1_1") (pintype "passive"))
      (node (ref "C21") (pin "1") (pinfunction "1_1") (pintype "passive"))
      (node (ref "IC1") (pin "1") (pinfunction "OUT_1") (pintype "passive"))
      (node (ref "IC1") (pin "2") (pinfunction "SENSE_2") (pintype "input"))
      (node (ref "JP11") (pin "2") (pinfunction "2_2") (pintype "passive"))
    )
    (net (code "68") (name "RF_IN") (class "Default")
      (node (ref "U2") (pin "1") (pinfunction "1_RF_IN_1") (pintype "bidirectional"))
      (node (ref "X1") (pin "1") (pinfunction "1_1") (pintype "passive"))
    )
    (net (code "69") (name "RUN") (class "Default")
      (node (ref "R1") (pin "1") (pinfunction "1_1") (pintype "passive"))
      (node (ref "R2") (pin "2") (pinfunction "2_2") (pintype "passive"))
      (node (ref "U1") (pin "13") (pinfunction "RUN_13") (pintype "bidirectional"))
    )
    (net (code "70") (name "SER_D_N") (class "Default")
      (node (ref "R13") (pin "2") (pinfunction "2_2") (pintype "passive"))
      (node (ref "U6") (pin "16") (pinfunction "USBDM_16") (pintype "bidirectional"))
    )
    (net (code "71") (name "SER_D_P") (class "Default")
      (node (ref "R16") (pin "2") (pinfunction "2_2") (pintype "passive"))
      (node (ref "U6") (pin "15") (pinfunction "USBDP_15") (pintype "bidirectional"))
    )
    (net (code "72") (name "SPI1_MISO") (class "Default")
      (node (ref "JP16") (pin "2") (pinfunction "2_2") (pintype "passive"))
      (node (ref "JP16") (pin "3") (pinfunction "3_3") (pintype "passive"))
      (node (ref "U3") (pin "12") (pinfunction "PA6_12") (pintype "bidirectional"))
    )
    (net (code "73") (name "SPI1_MOSI") (class "Default")
      (node (ref "JP17") (pin "2") (pinfunction "2_2") (pintype "passive"))
      (node (ref "JP17") (pin "3") (pinfunction "3_3") (pintype "passive"))
      (node (ref "U3") (pin "13") (pinfunction "PA7_13") (pintype "bidirectional"))
    )
    (net (code "74") (name "SPI1_NSS") (class "Default")
      (node (ref "JP14") (pin "2") (pinfunction "2_2") (pintype "passive"))
      (node (ref "JP14") (pin "3") (pinfunction "3_3") (pintype "passive"))
      (node (ref "U3") (pin "10") (pinfunction "PA4_10") (pintype "bidirectional"))
    )
    (net (code "75") (name "SPI1_SCK") (class "Default")
      (node (ref "JP15") (pin "2") (pinfunction "2_2") (pintype "passive"))
      (node (ref "JP15") (pin "3") (pinfunction "3_3") (pintype "passive"))
      (node (ref "U3") (pin "11") (pinfunction "PA5_11") (pintype "bidirectional"))
    )
    (net (code "76") (name "SWCLK") (class "Default")
      (node (ref "J1") (pin "2") (pinfunction "2_2") (pintype "passive"))
      (node (ref "U3") (pin "22") (pinfunction "PA14_22") (pintype "bidirectional"))
    )
    (net (code "77") (name "SWDIO") (class "Default")
      (node (ref "J1") (pin "4") (pinfunction "4_4") (pintype "passive"))
      (node (ref "U3") (pin "21") (pinfunction "PA13_21") (pintype "bidirectional"))
    )
    (net (code "78") (name "USART2_RX") (class "Default")
      (node (ref "JP8") (pin "2") (pinfunction "2_2") (pintype "passive"))
      (node (ref "JP8") (pin "3") (pinfunction "3_3") (pintype "passive"))
      (node (ref "U3") (pin "20") (pinfunction "PA10_20") (pintype "bidirectional"))
    )
    (net (code "79") (name "USART2_TX") (class "Default")
      (node (ref "JP9") (pin "2") (pinfunction "2_2") (pintype "passive"))
      (node (ref "JP9") (pin "3") (pinfunction "3_3") (pintype "passive"))
      (node (ref "U3") (pin "19") (pinfunction "PA9_19") (pintype "bidirectional"))
    )
    (net (code "80") (name "USBC_CC1") (class "Default")
      (node (ref "R14") (pin "1") (pinfunction "1_1") (pintype "passive"))
      (node (ref "U5") (pin "A5") (pinfunction "A5_CC1_A5") (pintype "bidirectional"))
    )
    (net (code "81") (name "USBC_CC2") (class "Default")
      (node (ref "R15") (pin "1") (pinfunction "1_1") (pintype "passive"))
      (node (ref "U5") (pin "B5") (pinfunction "B5_CC2_B5") (pintype "bidirectional"))
    )
    (net (code "82") (name "USBC_DN") (class "Default")
      (node (ref "CR2") (pin "3") (pinfunction "I/O2_2_3") (pintype "bidirectional"))
      (node (ref "U5") (pin "A7") (pinfunction "A7_DN1_A7") (pintype "bidirectional"))
      (node (ref "U5") (pin "B7") (pinfunction "B7_DN2_B7") (pintype "bidirectional"))
    )
    (net (code "83") (name "USBC_DP") (class "Default")
      (node (ref "CR2") (pin "1") (pinfunction "I/O1_2_1") (pintype "bidirectional"))
      (node (ref "U5") (pin "A6") (pinfunction "A6_DP1_A6") (pintype "bidirectional"))
      (node (ref "U5") (pin "B6") (pinfunction "B6_DP2_B6") (pintype "bidirectional"))
    )
    (net (code "84") (name "USBC_VBUS") (class "Default")
      (node (ref "C22") (pin "1") (pinfunction "1_1") (pintype "passive"))
      (node (ref "CR2") (pin "5") (pinfunction "VBUS_5") (pintype "power_in"))
      (node (ref "JP12") (pin "2") (pinfunction "2_2") (pintype "passive"))
      (node (ref "U5") (pin "A4") (pinfunction "A4_VBUS_A4") (pintype "bidirectional"))
      (node (ref "U5") (pin "A9") (pinfunction "A9_VBUS_A9") (pintype "bidirectional"))
      (node (ref "U5") (pin "B4") (pinfunction "B4_VBUS_B4") (pintype "bidirectional"))
      (node (ref "U5") (pin "B9") (pinfunction "B9_VBUS_B9") (pintype "bidirectional"))
    )
    (net (code "85") (name "USB_DM") (class "Default")
      (node (ref "CR1") (pin "1") (pinfunction "I/O1_2_1") (pintype "bidirectional"))
      (node (ref "J2") (pin "D-1") (pinfunction "D-_D-1") (pintype "bidirectional"))
    )
    (net (code "86") (name "USB_DP") (class "Default")
      (node (ref "CR1") (pin "3") (pinfunction "I/O2_2_3") (pintype "bidirectional"))
      (node (ref "J2") (pin "D+1") (pinfunction "D+_D+1") (pintype "bidirectional"))
    )
    (net (code "87") (name "USB_VBUS") (class "Default")
      (node (ref "C14") (pin "1") (pinfunction "1_1") (pintype "passive"))
      (node (ref "CR1") (pin "5") (pinfunction "VBUS_5") (pintype "power_in"))
      (node (ref "J2") (pin "VBUS1") (pinfunction "VBUS_VBUS1") (pintype "power_in"))
      (node (ref "U7") (pin "1") (pinfunction "IN_1") (pintype "input"))
      (node (ref "U7") (pin "3") (pinfunction "EN_3") (pintype "input"))
    )
    (net (code "88") (name "VAUX_3.3V") (class "Default")
      (node (ref "JP10") (pin "2") (pinfunction "2_2") (pintype "passive"))
      (node (ref "X7") (pin "2") (pinfunction "S_2") (pintype "passive"))
    )
    (net (code "89") (name "VAUX_5V") (class "Default")
      (node (ref "JP13") (pin "2") (pinfunction "2_2") (pintype "passive"))
      (node (ref "X6") (pin "3") (pinfunction "S_3") (pintype "passive"))
      (node (ref "X6") (pin "4") (pinfunction "S_4") (pintype "passive"))
    )
    (net (code "90") (name "VCC") (class "Default")
      (node (ref "C4") (pin "1") (pinfunction "1_1") (pintype "passive"))
      (node (ref "J3") (pin "5") (pinfunction "5_5") (pintype "passive"))
      (node (ref "U1") (pin "4") (pinfunction "VCC_4") (pintype "bidirectional"))
      (node (ref "U1") (pin "5") (pinfunction "OS1_5") (pintype "bidirectional"))
      (node (ref "U1") (pin "8") (pinfunction "MPP_8") (pintype "bidirectional"))
      (node (ref "U1") (pin "9") (pinfunction "SS2_9") (pintype "bidirectional"))
    )
    (net (code "91") (name "VIN") (class "Default")
      (node (ref "J3") (pin "2") (pinfunction "2_2") (pintype "passive"))
      (node (ref "JP1") (pin "1") (pinfunction "1_1") (pintype "passive"))
      (node (ref "U1") (pin "16") (pinfunction "VIN_16") (pintype "bidirectional"))
    )
    (net (code "92") (name "VOUT") (class "Default")
      (node (ref "C5") (pin "1") (pinfunction "1_1") (pintype "passive"))
      (node (ref "C6") (pin "1") (pinfunction "1_1") (pintype "passive"))
      (node (ref "JP3") (pin "2") (pinfunction "2_2") (pintype "passive"))
      (node (ref "R3") (pin "1") (pinfunction "1_1") (pintype "passive"))
      (node (ref "U1") (pin "2") (pinfunction "VOUT_2") (pintype "bidirectional"))
    )
    (net (code "93") (name "VSOLAR") (class "Default")
      (node (ref "C7") (pin "1") (pinfunction "1_1") (pintype "passive"))
      (node (ref "JP1") (pin "2") (pinfunction "2_2") (pintype "passive"))
      (node (ref "R1") (pin "2") (pinfunction "2_2") (pintype "passive"))
      (node (ref "SC1") (pin "1") (pinfunction "VPOS_1") (pintype "bidirectional"))
      (node (ref "SC2") (pin "1") (pinfunction "VPOS_1") (pintype "bidirectional"))
    )
    (net (code "94") (name "VSTORAGE") (class "Default")
      (node (ref "C1") (pin "1") (pinfunction "CAP_POS_1") (pintype "bidirectional"))
      (node (ref "C3") (pin "1") (pinfunction "1_1") (pintype "passive"))
      (node (ref "D2") (pin "3") (pinfunction "3_3") (pintype "bidirectional"))
      (node (ref "J3") (pin "3") (pinfunction "3_3") (pintype "passive"))
      (node (ref "JP2") (pin "2") (pinfunction "2_2") (pintype "passive"))
      (node (ref "R9") (pin "2") (pinfunction "2_2") (pintype "passive"))
    )
    (net (code "95") (name "unconnected-(J1-Pad3)") (class "Default")
      (node (ref "J1") (pin "3") (pinfunction "3_3") (pintype "passive"))
    )
    (net (code "96") (name "unconnected-(J1-Pad9)") (class "Default")
      (node (ref "J1") (pin "9") (pinfunction "9_9") (pintype "passive"))
    )
    (net (code "97") (name "unconnected-(J1-Pad10)") (class "Default")
      (node (ref "J1") (pin "10") (pinfunction "10_10") (pintype "passive"))
    )
    (net (code "98") (name "unconnected-(J2-USBID-PadID1)") (class "Default")
      (node (ref "J2") (pin "ID1") (pinfunction "USBID_ID1") (pintype "bidirectional"))
    )
    (net (code "99") (name "unconnected-(J3-Pad6)") (class "Default")
      (node (ref "J3") (pin "6") (pinfunction "6_6") (pintype "passive"))
    )
    (net (code "100") (name "unconnected-(J3-Pad7)") (class "Default")
      (node (ref "J3") (pin "7") (pinfunction "7_7") (pintype "passive"))
    )
    (net (code "101") (name "unconnected-(J4-Pad6)") (class "Default")
      (node (ref "J4") (pin "6") (pinfunction "6_6") (pintype "passive"))
    )
    (net (code "102") (name "unconnected-(J4-Pad7)") (class "Default")
      (node (ref "J4") (pin "7") (pinfunction "7_7") (pintype "passive"))
    )
    (net (code "103") (name "unconnected-(J5-Pad5)") (class "Default")
      (node (ref "J5") (pin "5") (pinfunction "5_5") (pintype "passive"))
    )
    (net (code "104") (name "unconnected-(J5-Pad6)") (class "Default")
      (node (ref "J5") (pin "6") (pinfunction "6_6") (pintype "passive"))
    )
    (net (code "105") (name "unconnected-(J5-Pad7)") (class "Default")
      (node (ref "J5") (pin "7") (pinfunction "7_7") (pintype "passive"))
    )
    (net (code "106") (name "unconnected-(SW1-A0-Pad1)") (class "Default")
      (node (ref "SW1") (pin "1") (pinfunction "A0_1") (pintype "bidirectional"))
    )
    (net (code "107") (name "unconnected-(SW1-B0-Pad3)") (class "Default")
      (node (ref "SW1") (pin "3") (pinfunction "B0_3") (pintype "bidirectional"))
    )
    (net (code "108") (name "unconnected-(SW2-A0-Pad1)") (class "Default")
      (node (ref "SW2") (pin "1") (pinfunction "A0_1") (pintype "bidirectional"))
    )
    (net (code "109") (name "unconnected-(SW2-B0-Pad3)") (class "Default")
      (node (ref "SW2") (pin "3") (pinfunction "B0_3") (pintype "bidirectional"))
    )
    (net (code "110") (name "unconnected-(U1-ILMSEL-Pad12)") (class "Default")
      (node (ref "U1") (pin "12") (pinfunction "ILMSEL_12") (pintype "bidirectional"))
    )
    (net (code "111") (name "unconnected-(U2-3_RESERVED-Pad3)") (class "Default")
      (node (ref "U2") (pin "3") (pinfunction "3_RESERVED_3") (pintype "bidirectional"))
    )
    (net (code "112") (name "unconnected-(U2-4_RESERVED-Pad4)") (class "Default")
      (node (ref "U2") (pin "4") (pinfunction "4_RESERVED_4") (pintype "bidirectional"))
    )
    (net (code "113") (name "unconnected-(U2-10_RESERVED-Pad10)") (class "Default")
      (node (ref "U2") (pin "10") (pinfunction "10_RESERVED_10") (pintype "bidirectional"))
    )
    (net (code "114") (name "unconnected-(U2-11_RESERVED-Pad11)") (class "Default")
      (node (ref "U2") (pin "11") (pinfunction "11_RESERVED_11") (pintype "bidirectional"))
    )
    (net (code "115") (name "unconnected-(U2-12_PIO14{slash}ANT_DET-Pad12)") (class "Default")
      (node (ref "U2") (pin "12") (pinfunction "12_PIO14/ANT_DET_12") (pintype "bidirectional"))
    )
    (net (code "116") (name "unconnected-(U2-13_PIO13{slash}EXTINT-Pad13)") (class "Default")
      (node (ref "U2") (pin "13") (pinfunction "13_PIO13/EXTINT_13") (pintype "bidirectional"))
    )
    (net (code "117") (name "unconnected-(U2-17_RESERVED-Pad17)") (class "Default")
      (node (ref "U2") (pin "17") (pinfunction "17_RESERVED_17") (pintype "bidirectional"))
    )
    (net (code "118") (name "unconnected-(U2-22_SQI_D0-Pad22)") (class "Default")
      (node (ref "U2") (pin "22") (pinfunction "22_SQI_D0_22") (pintype "bidirectional"))
    )
    (net (code "119") (name "unconnected-(U2-23_SQI_CLK-Pad23)") (class "Default")
      (node (ref "U2") (pin "23") (pinfunction "23_SQI_CLK_23") (pintype "bidirectional"))
    )
    (net (code "120") (name "unconnected-(U2-24_SQI_D2-Pad24)") (class "Default")
      (node (ref "U2") (pin "24") (pinfunction "24_SQI_D2_24") (pintype "bidirectional"))
    )
    (net (code "121") (name "unconnected-(U2-25_SQI_D1-Pad25)") (class "Default")
      (node (ref "U2") (pin "25") (pinfunction "25_SQI_D1_25") (pintype "bidirectional"))
    )
    (net (code "122") (name "unconnected-(U2-27_SQI_D3-Pad27)") (class "Default")
      (node (ref "U2") (pin "27") (pinfunction "27_SQI_D3_27") (pintype "bidirectional"))
    )
    (net (code "123") (name "unconnected-(U2-28_RESERVED-Pad28)") (class "Default")
      (node (ref "U2") (pin "28") (pinfunction "28_RESERVED_28") (pintype "bidirectional"))
    )
    (net (code "124") (name "unconnected-(U2-28_SQI_CS_N-Pad26)") (class "Default")
      (node (ref "U2") (pin "26") (pinfunction "28_SQI_CS_N_26") (pintype "bidirectional"))
    )
    (net (code "125") (name "unconnected-(U2-29_SCL{slash}SPI_CLK-Pad29)") (class "Default")
      (node (ref "U2") (pin "29") (pinfunction "29_SCL/SPI_CLK_29") (pintype "bidirectional"))
    )
    (net (code "126") (name "unconnected-(U2-30_SDA{slash}SPI_CS_N-Pad30)") (class "Default")
      (node (ref "U2") (pin "30") (pinfunction "30_SDA/SPI_CS_N_30") (pintype "bidirectional"))
    )
    (net (code "127") (name "unconnected-(U2-31_TIMEPULSE-Pad31)") (class "Default")
      (node (ref "U2") (pin "31") (pinfunction "31_TIMEPULSE_31") (pintype "bidirectional"))
    )
    (net (code "128") (name "unconnected-(U2-32_D_SEL-Pad32)") (class "Default")
      (node (ref "U2") (pin "32") (pinfunction "32_D_SEL_32") (pintype "bidirectional"))
    )
    (net (code "129") (name "unconnected-(U2-33_SAFEBOOT_N-Pad33)") (class "Default")
      (node (ref "U2") (pin "33") (pinfunction "33_SAFEBOOT_N_33") (pintype "bidirectional"))
    )
    (net (code "130") (name "unconnected-(U2-34_ANT_OK-Pad34)") (class "Default")
      (node (ref "U2") (pin "34") (pinfunction "34_ANT_OK_34") (pintype "bidirectional"))
    )
    (net (code "131") (name "unconnected-(U2-35_ANT_OFF-Pad35)") (class "Default")
      (node (ref "U2") (pin "35") (pinfunction "35_ANT_OFF_35") (pintype "bidirectional"))
    )
    (net (code "132") (name "unconnected-(U2-36_RESERVED-Pad36)") (class "Default")
      (node (ref "U2") (pin "36") (pinfunction "36_RESERVED_36") (pintype "bidirectional"))
    )
    (net (code "133") (name "unconnected-(U3-PA15-Pad23)") (class "Default")
      (node (ref "U3") (pin "23") (pinfunction "PA15_23") (pintype "bidirectional"))
    )
    (net (code "134") (name "unconnected-(U3-PB3-Pad24)") (class "Default")
      (node (ref "U3") (pin "24") (pinfunction "PB3_24") (pintype "bidirectional"))
    )
    (net (code "135") (name "unconnected-(U3-PB4-Pad25)") (class "Default")
      (node (ref "U3") (pin "25") (pinfunction "PB4_25") (pintype "bidirectional"))
    )
    (net (code "136") (name "unconnected-(U3-PB5-Pad26)") (class "Default")
      (node (ref "U3") (pin "26") (pinfunction "PB5_26") (pintype "bidirectional"))
    )
    (net (code "137") (name "unconnected-(U3-PB6-Pad27)") (class "Default")
      (node (ref "U3") (pin "27") (pinfunction "PB6_27") (pintype "bidirectional"))
    )
    (net (code "138") (name "unconnected-(U3-PB7-Pad28)") (class "Default")
      (node (ref "U3") (pin "28") (pinfunction "PB7_28") (pintype "bidirectional"))
    )
    (net (code "139") (name "unconnected-(U4-GPIO0-Pad9)") (class "Default")
      (node (ref "U4") (pin "9") (pinfunction "GPIO0_9") (pintype "bidirectional"))
    )
    (net (code "140") (name "unconnected-(U4-GPIO2-Pad19)") (class "Default")
      (node (ref "U4") (pin "19") (pinfunction "GPIO2_19") (pintype "bidirectional"))
    )
    (net (code "141") (name "unconnected-(U4-GPIO3-Pad20)") (class "Default")
      (node (ref "U4") (pin "20") (pinfunction "GPIO3_20") (pintype "bidirectional"))
    )
    (net (code "142") (name "unconnected-(U4-NC -Pad5)") (class "Default")
      (node (ref "U4") (pin "5") (pinfunction "NC _5") (pintype "bidirectional"))
    )
    (net (code "143") (name "unconnected-(U4-RXN-Pad3)") (class "Default")
      (node (ref "U4") (pin "3") (pinfunction "RXN_3") (pintype "bidirectional"))
    )
    (net (code "144") (name "unconnected-(U4-RXP-Pad2)") (class "Default")
      (node (ref "U4") (pin "2") (pinfunction "RXP_2") (pintype "bidirectional"))
    )
    (net (code "145") (name "unconnected-(U4-TXRAMP-Pad7)") (class "Default")
      (node (ref "U4") (pin "7") (pinfunction "TXRAMP_7") (pintype "bidirectional"))
    )
    (net (code "146") (name "unconnected-(U5-A2_SSTXP1-PadA2)") (class "Default")
      (node (ref "U5") (pin "A2") (pinfunction "A2_SSTXP1_A2") (pintype "bidirectional"))
    )
    (net (code "147") (name "unconnected-(U5-A3_SSTXN1-PadA3)") (class "Default")
      (node (ref "U5") (pin "A3") (pinfunction "A3_SSTXN1_A3") (pintype "bidirectional"))
    )
    (net (code "148") (name "unconnected-(U5-A8_SBU1-PadA8)") (class "Default")
      (node (ref "U5") (pin "A8") (pinfunction "A8_SBU1_A8") (pintype "bidirectional"))
    )
    (net (code "149") (name "unconnected-(U5-A10_SSRXN2-PadA10)") (class "Default")
      (node (ref "U5") (pin "A10") (pinfunction "A10_SSRXN2_A10") (pintype "bidirectional"))
    )
    (net (code "150") (name "unconnected-(U5-A11_SSRXP2-PadA11)") (class "Default")
      (node (ref "U5") (pin "A11") (pinfunction "A11_SSRXP2_A11") (pintype "bidirectional"))
    )
    (net (code "151") (name "unconnected-(U5-B2_SSTXP2-PadB2)") (class "Default")
      (node (ref "U5") (pin "B2") (pinfunction "B2_SSTXP2_B2") (pintype "bidirectional"))
    )
    (net (code "152") (name "unconnected-(U5-B3_SSTXN2-PadB3)") (class "Default")
      (node (ref "U5") (pin "B3") (pinfunction "B3_SSTXN2_B3") (pintype "bidirectional"))
    )
    (net (code "153") (name "unconnected-(U5-B8_SBU2-PadB8)") (class "Default")
      (node (ref "U5") (pin "B8") (pinfunction "B8_SBU2_B8") (pintype "bidirectional"))
    )
    (net (code "154") (name "unconnected-(U5-B10_SSRXN1-PadB10)") (class "Default")
      (node (ref "U5") (pin "B10") (pinfunction "B10_SSRXN1_B10") (pintype "bidirectional"))
    )
    (net (code "155") (name "unconnected-(U5-B11_SSRXP1-PadB11)") (class "Default")
      (node (ref "U5") (pin "B11") (pinfunction "B11_SSRXP1_B11") (pintype "bidirectional"))
    )
    (net (code "156") (name "unconnected-(U6-3V3OUT-Pad17)") (class "Default")
      (node (ref "U6") (pin "17") (pinfunction "3V3OUT_17") (pintype "output"))
    )
    (net (code "157") (name "unconnected-(U6-CTS-Pad11)") (class "Default")
      (node (ref "U6") (pin "11") (pinfunction "CTS_11") (pintype "input"))
    )
    (net (code "158") (name "unconnected-(U6-DCD-Pad10)") (class "Default")
      (node (ref "U6") (pin "10") (pinfunction "DCD_10") (pintype "input"))
    )
    (net (code "159") (name "unconnected-(U6-DSR-Pad9)") (class "Default")
      (node (ref "U6") (pin "9") (pinfunction "DSR_9") (pintype "input"))
    )
    (net (code "160") (name "unconnected-(U6-DTR-Pad2)") (class "Default")
      (node (ref "U6") (pin "2") (pinfunction "DTR_2") (pintype "output"))
    )
    (net (code "161") (name "unconnected-(U6-OSCI-Pad27)") (class "Default")
      (node (ref "U6") (pin "27") (pinfunction "OSCI_27") (pintype "input"))
    )
    (net (code "162") (name "unconnected-(U6-OSCO-Pad28)") (class "Default")
      (node (ref "U6") (pin "28") (pinfunction "OSCO_28") (pintype "output"))
    )
    (net (code "163") (name "unconnected-(U6-PWREN-Pad14)") (class "Default")
      (node (ref "U6") (pin "14") (pinfunction "PWREN_14") (pintype "input"))
    )
    (net (code "164") (name "unconnected-(U6-RESET-Pad19)") (class "Default")
      (node (ref "U6") (pin "19") (pinfunction "RESET_19") (pintype "input"))
    )
    (net (code "165") (name "unconnected-(U6-RI-Pad6)") (class "Default")
      (node (ref "U6") (pin "6") (pinfunction "RI_6") (pintype "input"))
    )
    (net (code "166") (name "unconnected-(U6-RTS-Pad3)") (class "Default")
      (node (ref "U6") (pin "3") (pinfunction "RTS_3") (pintype "output"))
    )
    (net (code "167") (name "unconnected-(U6-SLEEP-Pad12)") (class "Default")
      (node (ref "U6") (pin "12") (pinfunction "SLEEP_12") (pintype "input"))
    )
    (net (code "168") (name "unconnected-(U6-TXDEN-Pad13)") (class "Default")
      (node (ref "U6") (pin "13") (pinfunction "TXDEN_13") (pintype "input"))
    )
    (net (code "169") (name "unconnected-(U7-NC-Pad4)") (class "Default")
      (node (ref "U7") (pin "4") (pinfunction "NC_4") (pintype "no_connect"))
    )
    (net (code "170") (name "unconnected-(X8-Pad2)") (class "Default")
      (node (ref "X8") (pin "2") (pinfunction "2_2") (pintype "passive"))
    )
    (net (code "171") (name "unconnected-(X8-Pad4)") (class "Default")
      (node (ref "X8") (pin "4") (pinfunction "4_4") (pintype "passive"))
    )
  )
)
